# Central_Board.net
KiCad netlist of a schematic drawn in EAGLE
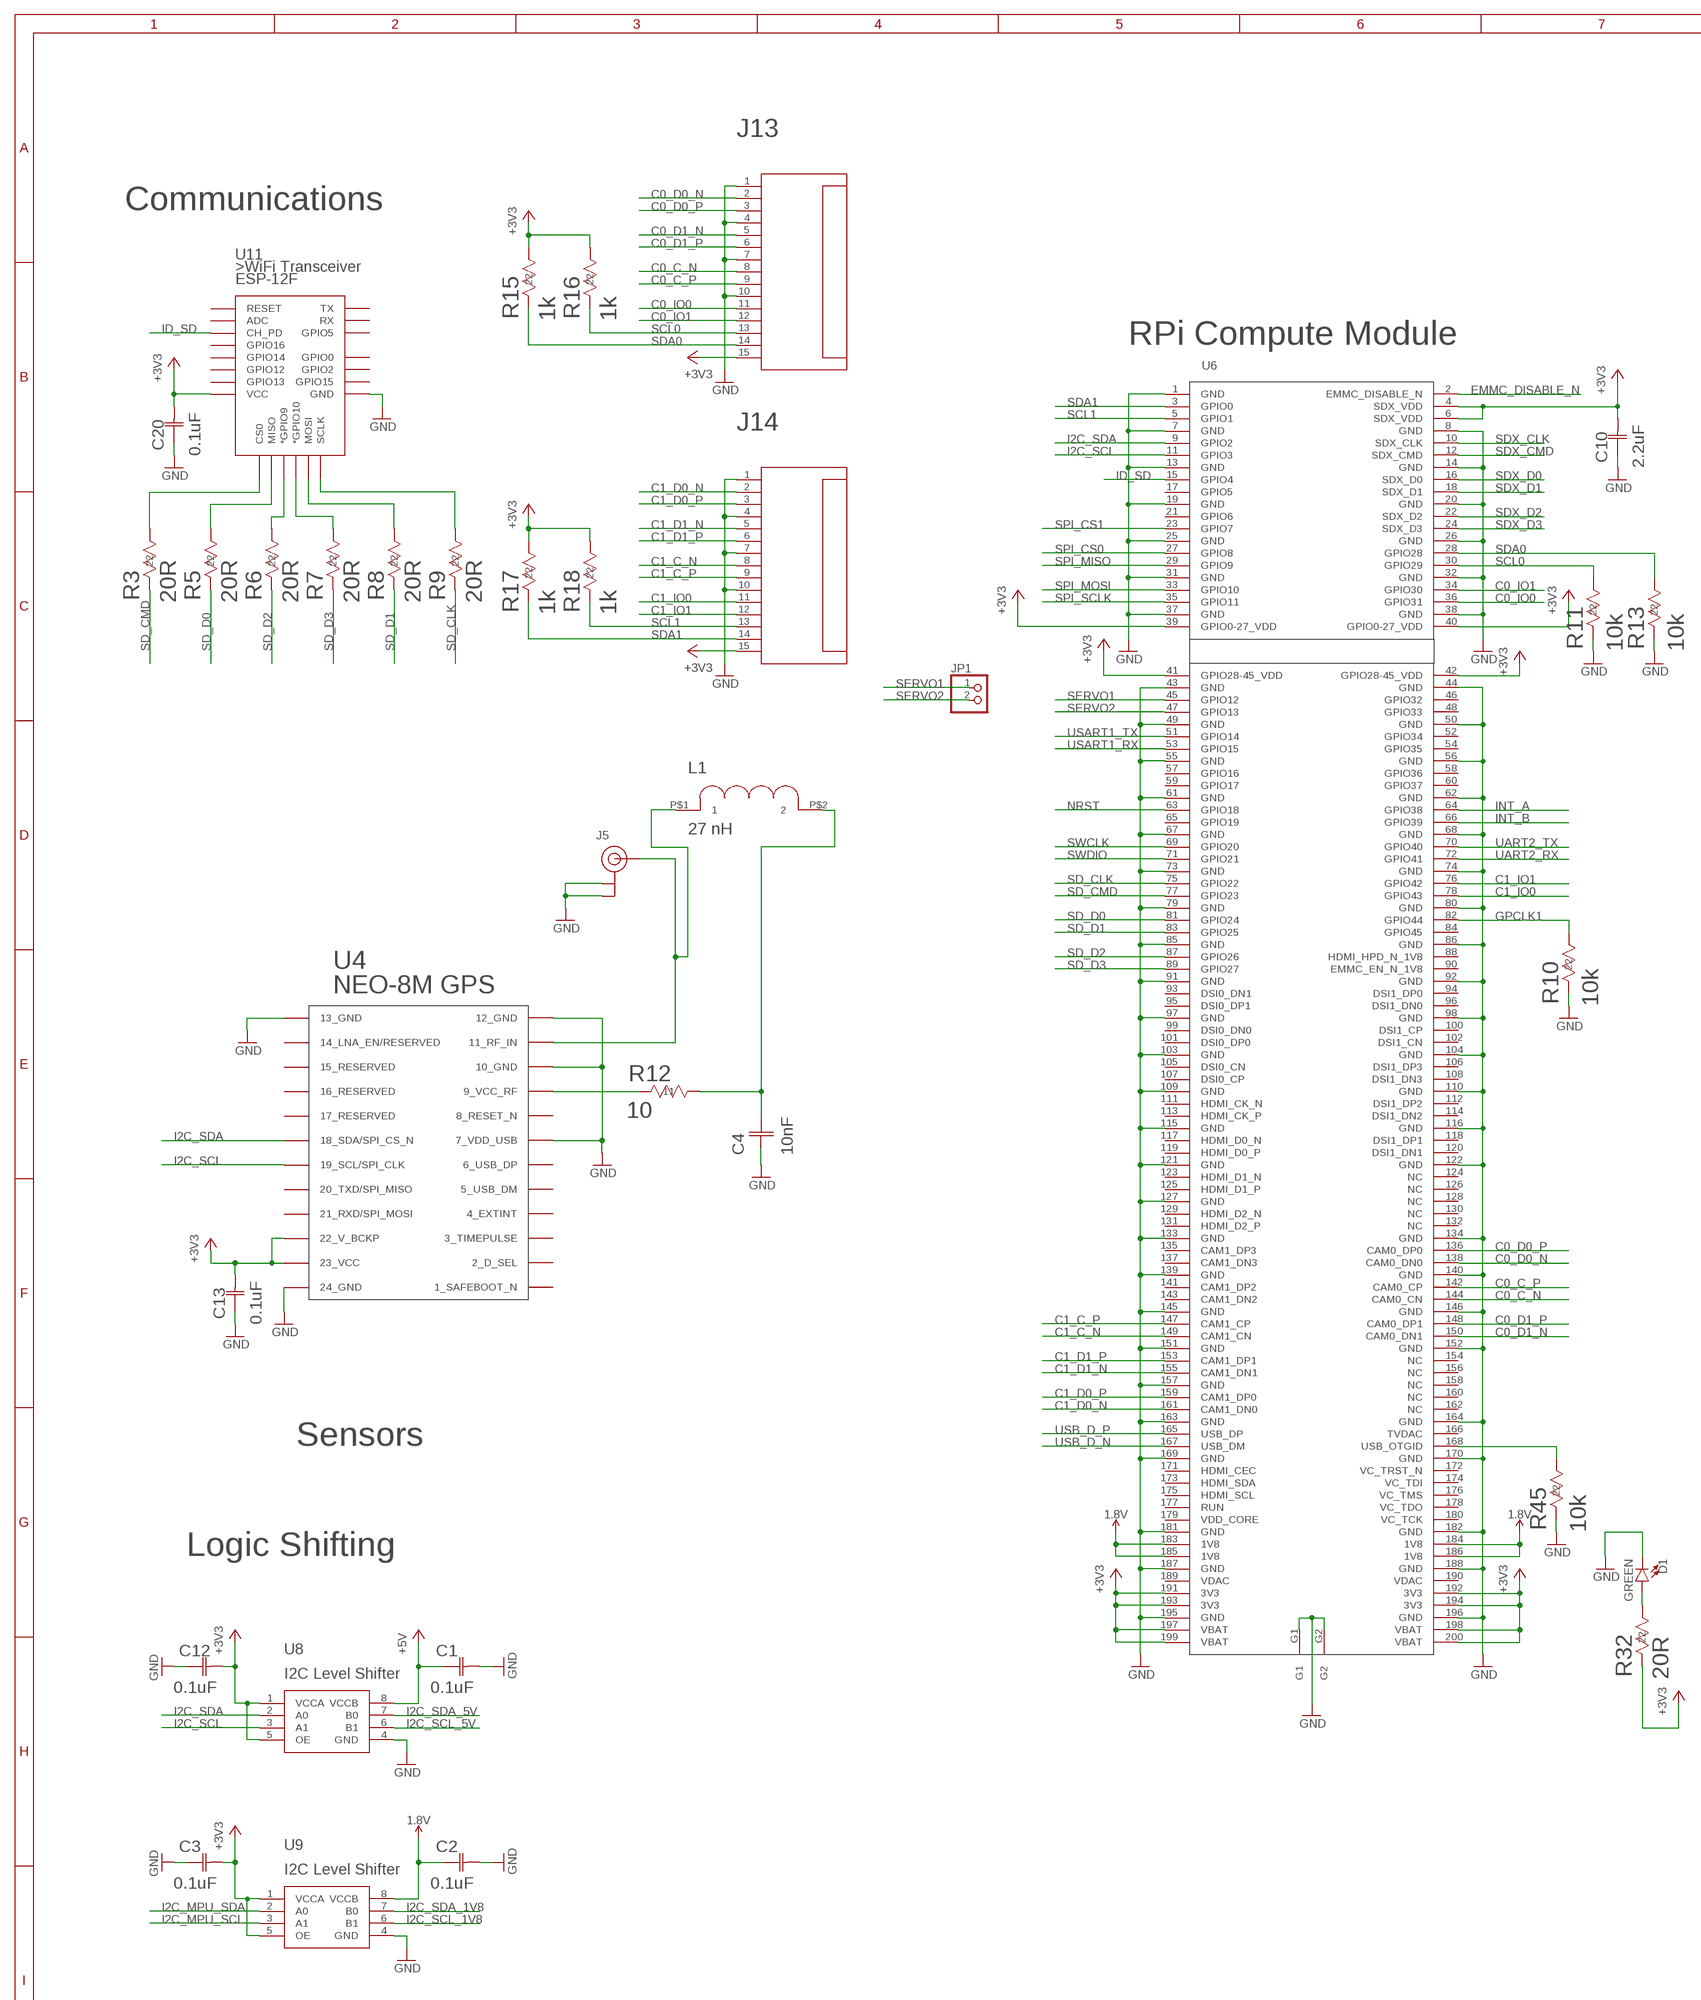
[diagram p0: schematic, sheet 1, part 1 of 2]
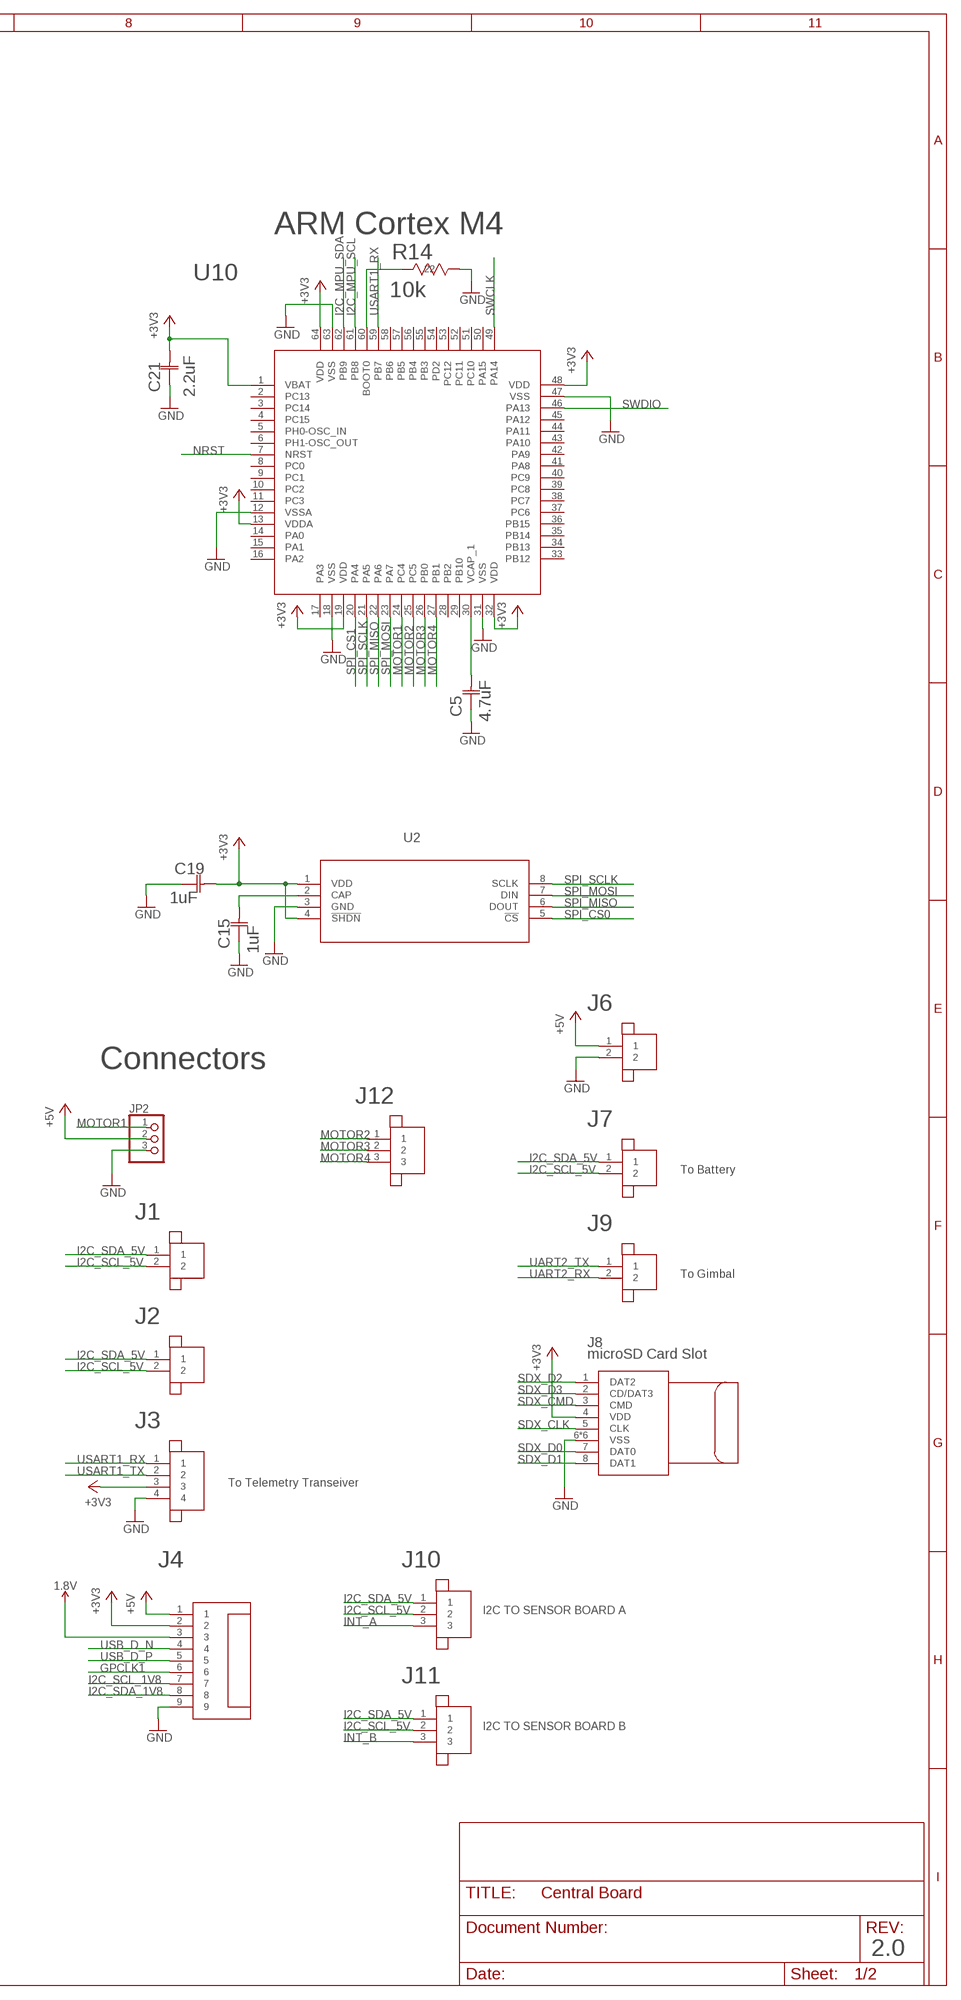
[diagram p1: schematic, sheet 1, part 2 of 2]
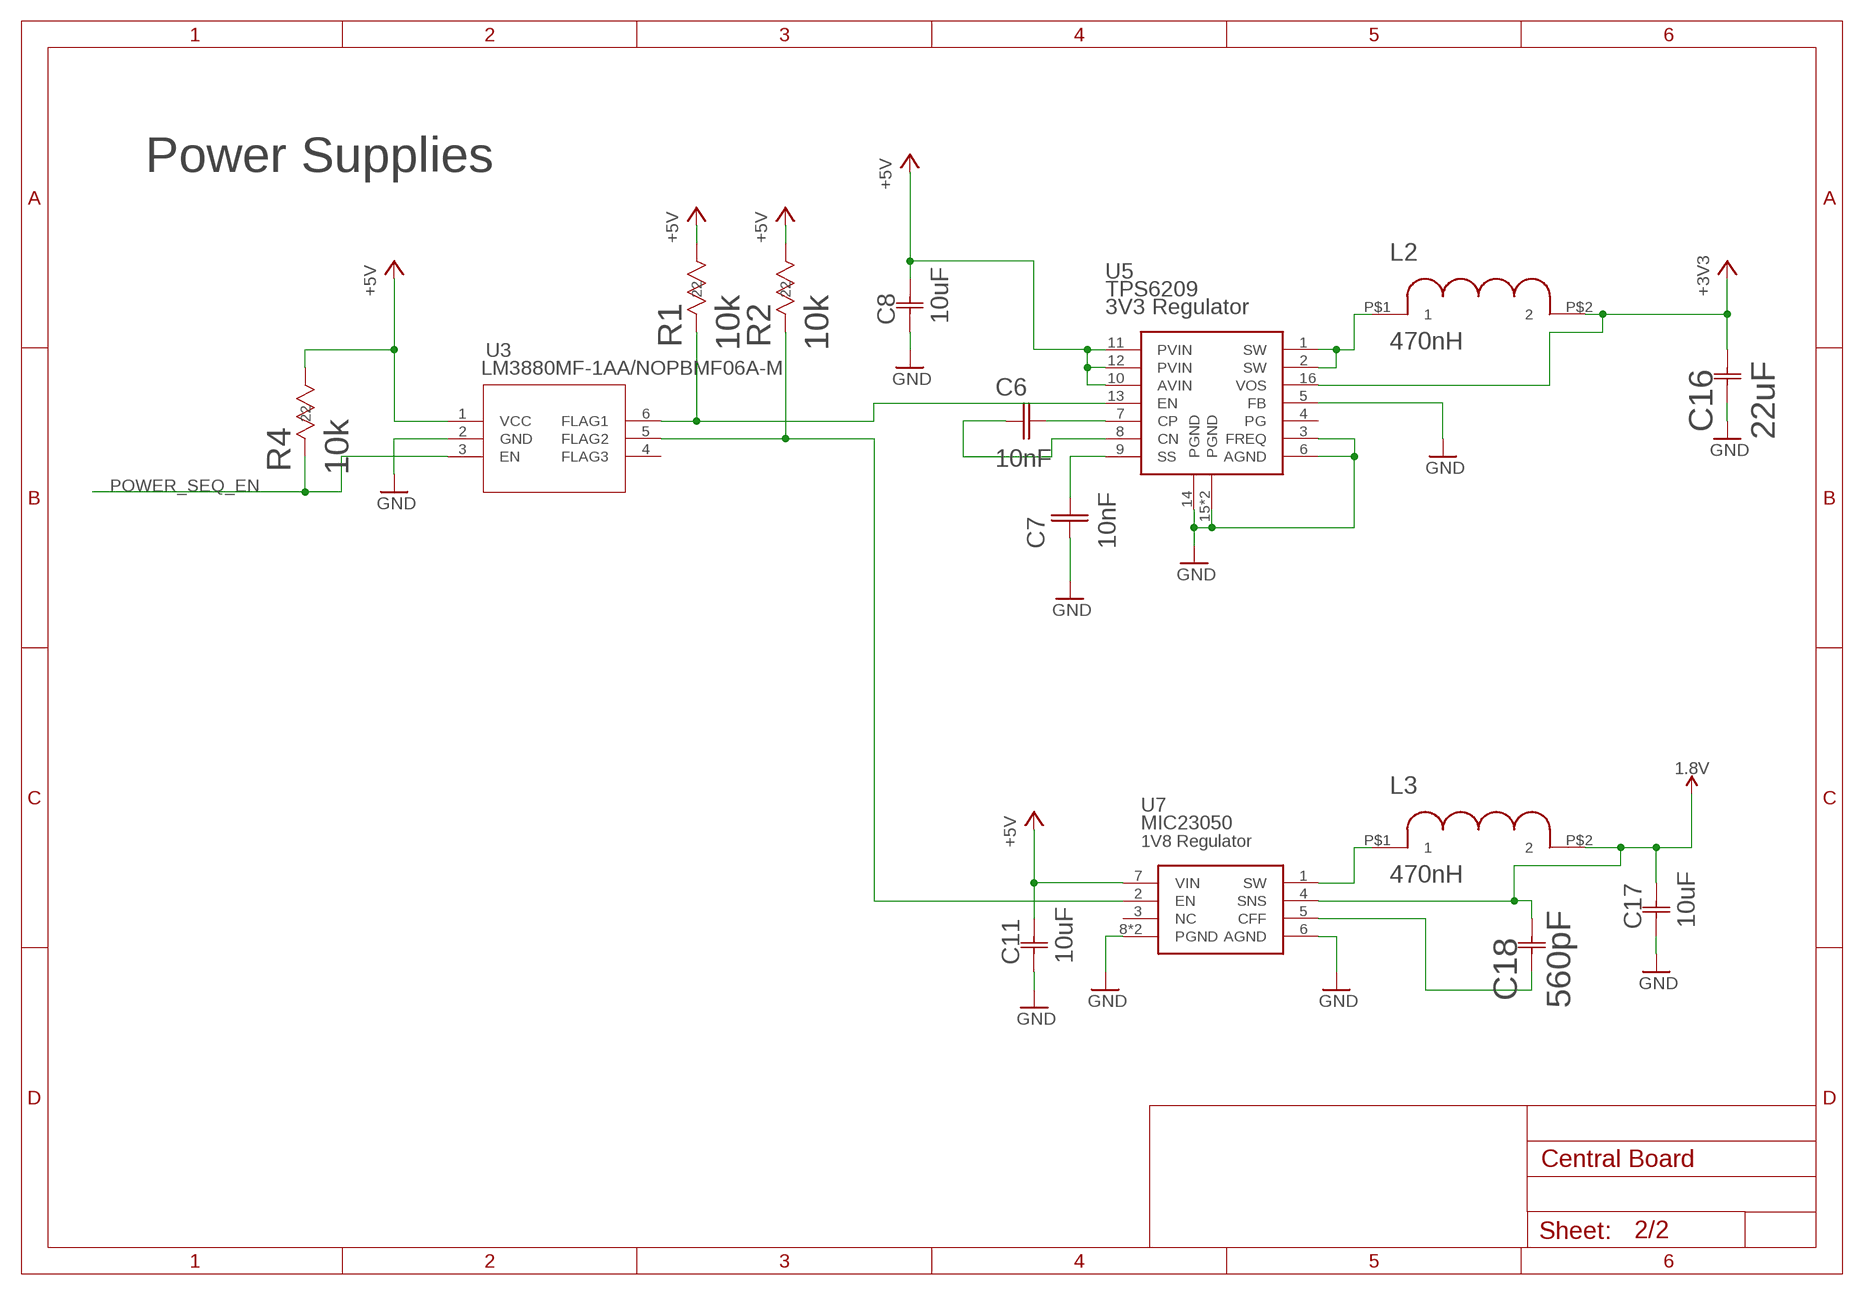
[diagram p2: schematic, sheet 2]

(export (version "E")
  (design (tool "Eeschema 10.0.6"))
  (components
    (comp (ref "C6")
      (value "10nF")
      (footprint "eagle-import:0603_CAPACITOR")
      (libsource (lib "eagle-import") (part "10NF_CAPACITOR"))
    )
    (comp (ref "C7")
      (value "10nF")
      (footprint "eagle-import:0603_CAPACITOR")
      (libsource (lib "eagle-import") (part "10NF_CAPACITOR"))
    )
    (comp (ref "C8")
      (value "10uF")
      (footprint "eagle-import:G-21")
      (fields
        (field (name "MANUFACTURER_PART_NUMBER") "GRM21BR60J106ME19L")
        (field (name "COPYRIGHT") "Copyright C 2015 Accelerated Designs. All rights reserved")
      )
      (libsource (lib "eagle-import") (part "GRM21BR60J106ME19L"))
    )
    (comp (ref "C11")
      (value "10uF")
      (footprint "eagle-import:G-21")
      (fields
        (field (name "MANUFACTURER_PART_NUMBER") "GRM21BR60J106ME19L")
        (field (name "COPYRIGHT") "Copyright C 2015 Accelerated Designs. All rights reserved")
      )
      (libsource (lib "eagle-import") (part "GRM21BR60J106ME19L"))
    )
    (comp (ref "C16")
      (value "22uF")
      (footprint "eagle-import:G-21")
      (fields
        (field (name "MANUFACTURER_PART_NUMBER") "GRM21BR60J226ME39L")
        (field (name "COPYRIGHT") "Copyright C 2015 Accelerated Designs. All rights reserved")
      )
      (libsource (lib "eagle-import") (part "GRM21BR60J226ME39L"))
    )
    (comp (ref "C17")
      (value "10uF")
      (footprint "eagle-import:G-21")
      (fields
        (field (name "MANUFACTURER_PART_NUMBER") "GRM21BR60J106ME19L")
        (field (name "COPYRIGHT") "Copyright C 2015 Accelerated Designs. All rights reserved")
      )
      (libsource (lib "eagle-import") (part "GRM21BR60J106ME19L"))
    )
    (comp (ref "C18")
      (value "560pF")
      (footprint "eagle-import:CC0402N-M")
      (fields (field (name "MANUFACTURER_PART_NUMBER") "CC0402KRX7R9BB561"))
      (libsource (lib "eagle-import") (part "CC0402KRX7R9BB561CC0402N-M"))
    )
    (comp (ref "L2")
      (value "470nH")
      (footprint "eagle-import:1008_INDUCTOR")
      (libsource (lib "eagle-import") (part "470NH_INDUCTOR"))
    )
    (comp (ref "L3")
      (value "470nH")
      (footprint "eagle-import:1008_INDUCTOR")
      (libsource (lib "eagle-import") (part "470NH_INDUCTOR"))
    )
    (comp (ref "R1")
      (value "10k")
      (footprint "eagle-import:RC0805N")
      (fields
        (field (name "DIGIKEYPARTNUMBER") "P10KDATRND")
        (field (name "MANUFACTURER_PART_NUMBER") "ERA6AEB103V")
        (field (name "TOLERANCE") "0.1%")
        (field (name "COPYRIGHT") "Copyright C 2015 Accelerated Designs. All rights reserved")
      )
      (libsource (lib "eagle-import") (part "ERA-6AEB103V"))
    )
    (comp (ref "R2")
      (value "10k")
      (footprint "eagle-import:RC0805N")
      (fields
        (field (name "DIGIKEYPARTNUMBER") "P10KDATRND")
        (field (name "MANUFACTURER_PART_NUMBER") "ERA6AEB103V")
        (field (name "TOLERANCE") "0.1%")
        (field (name "COPYRIGHT") "Copyright C 2015 Accelerated Designs. All rights reserved")
      )
      (libsource (lib "eagle-import") (part "ERA-6AEB103V"))
    )
    (comp (ref "R4")
      (value "10k")
      (footprint "eagle-import:RC0805N")
      (fields
        (field (name "DIGIKEYPARTNUMBER") "P10KDATRND")
        (field (name "MANUFACTURER_PART_NUMBER") "ERA6AEB103V")
        (field (name "TOLERANCE") "0.1%")
        (field (name "COPYRIGHT") "Copyright C 2015 Accelerated Designs. All rights reserved")
      )
      (libsource (lib "eagle-import") (part "ERA-6AEB103V"))
    )
    (comp (ref "U3")
      (value "LM3880MF-1AA/NOPBMF06A-M")
      (footprint "eagle-import:MF06A-M")
      (fields (field (name "MANUFACTURER_PART_NUMBER") "lm3880mf1aaNOPB"))
      (libsource (lib "eagle-import") (part "LM3880MF-1AA/NOPBMF06A-M"))
    )
    (comp (ref "U5")
      (value "TPS6209")
      (footprint "eagle-import:VQFN16")
      (libsource (lib "eagle-import") (part "TPS6209"))
    )
    (comp (ref "U7")
      (value "MIC23050")
      (footprint "eagle-import:MLF(ML)_8PIN")
      (libsource (lib "eagle-import") (part "MIC23050"))
    )
    (comp (ref "C1")
      (value "0.1uF")
      (footprint "eagle-import:0805")
      (fields
        (field (name "MANUFACTURER_PART_NUMBER") "08055C104KAT2A")
        (field (name "COPYRIGHT") "Copyright C 2015 Accelerated Designs. All rights reserved")
      )
      (libsource (lib "eagle-import") (part "08055C104KAT2A"))
    )
    (comp (ref "C2")
      (value "0.1uF")
      (footprint "eagle-import:0805")
      (fields
        (field (name "MANUFACTURER_PART_NUMBER") "08055C104KAT2A")
        (field (name "COPYRIGHT") "Copyright C 2015 Accelerated Designs. All rights reserved")
      )
      (libsource (lib "eagle-import") (part "08055C104KAT2A"))
    )
    (comp (ref "C3")
      (value "0.1uF")
      (footprint "eagle-import:0805")
      (fields
        (field (name "MANUFACTURER_PART_NUMBER") "08055C104KAT2A")
        (field (name "COPYRIGHT") "Copyright C 2015 Accelerated Designs. All rights reserved")
      )
      (libsource (lib "eagle-import") (part "08055C104KAT2A"))
    )
    (comp (ref "C4")
      (value "10nF")
      (footprint "eagle-import:0603_CAPACITOR")
      (libsource (lib "eagle-import") (part "10NF_CAPACITOR"))
    )
    (comp (ref "C5")
      (value "4.7uF")
      (footprint "eagle-import:0603-M")
      (fields (field (name "MANUFACTURER_PART_NUMBER") "06036D475KAT2A"))
      (libsource (lib "eagle-import") (part "06036D475KAT2A0603-M"))
    )
    (comp (ref "C10")
      (value "2.2uF")
      (footprint "eagle-import:G-188-M")
      (fields
        (field (name "MANUFACTURER_PART_NUMBER") "GRM188R61C225KE15J")
        (field (name "COPYRIGHT") "Copyright C 2015 Accelerated Designs. All rights reserved")
      )
      (libsource (lib "eagle-import") (part "GRM188R61C225KE15JG-188-M"))
    )
    (comp (ref "C12")
      (value "0.1uF")
      (footprint "eagle-import:0805")
      (fields
        (field (name "MANUFACTURER_PART_NUMBER") "08055C104KAT2A")
        (field (name "COPYRIGHT") "Copyright C 2015 Accelerated Designs. All rights reserved")
      )
      (libsource (lib "eagle-import") (part "08055C104KAT2A"))
    )
    (comp (ref "C13")
      (value "0.1uF")
      (footprint "eagle-import:0805")
      (fields
        (field (name "MANUFACTURER_PART_NUMBER") "08055C104KAT2A")
        (field (name "COPYRIGHT") "Copyright C 2015 Accelerated Designs. All rights reserved")
      )
      (libsource (lib "eagle-import") (part "08055C104KAT2A"))
    )
    (comp (ref "C15")
      (value "1uF")
      (footprint "eagle-import:YAG_CC0805")
      (fields
        (field (name "MANUFACTURER_PART_NUMBER") "CC0805KKX7R7BB105")
        (field (name "COPYRIGHT") "Copyright C 2015 Accelerated Designs. All rights reserved")
      )
      (libsource (lib "eagle-import") (part "CC0805KKX7R7BB105"))
    )
    (comp (ref "C19")
      (value "1uF")
      (footprint "eagle-import:YAG_CC0805")
      (fields
        (field (name "MANUFACTURER_PART_NUMBER") "CC0805KKX7R7BB105")
        (field (name "COPYRIGHT") "Copyright C 2015 Accelerated Designs. All rights reserved")
      )
      (libsource (lib "eagle-import") (part "CC0805KKX7R7BB105"))
    )
    (comp (ref "C20")
      (value "0.1uF")
      (footprint "eagle-import:0805")
      (fields
        (field (name "MANUFACTURER_PART_NUMBER") "08055C104KAT2A")
        (field (name "COPYRIGHT") "Copyright C 2015 Accelerated Designs. All rights reserved")
      )
      (libsource (lib "eagle-import") (part "08055C104KAT2A"))
    )
    (comp (ref "C21")
      (value "2.2uF")
      (footprint "eagle-import:G-188-M")
      (fields
        (field (name "MANUFACTURER_PART_NUMBER") "GRM188R61C225KE15J")
        (field (name "COPYRIGHT") "Copyright C 2015 Accelerated Designs. All rights reserved")
      )
      (libsource (lib "eagle-import") (part "GRM188R61C225KE15JG-188-M"))
    )
    (comp (ref "D1")
      (value "GREEN")
      (footprint "eagle-import:LED-0603")
      (libsource (lib "eagle-import") (part "LED-GREEN0603"))
    )
    (comp (ref "J1")
      (value "JST_SH_2POS")
      (footprint "eagle-import:JST_SH_2POS")
      (libsource (lib "eagle-import") (part "JST_SH_2POS"))
    )
    (comp (ref "J2")
      (value "JST_SH_2POS")
      (footprint "eagle-import:JST_SH_2POS")
      (libsource (lib "eagle-import") (part "JST_SH_2POS"))
    )
    (comp (ref "J3")
      (value "JST_SH_4POS")
      (footprint "eagle-import:JST_SH_4POS")
      (libsource (lib "eagle-import") (part "JST_SH_4POS"))
    )
    (comp (ref "J4")
      (value "9POS_FFC_CONNECTOR")
      (footprint "eagle-import:9POS_FFC_CONNECTOR")
      (libsource (lib "eagle-import") (part "9POS_FFC_CONNECTOR"))
    )
    (comp (ref "J5")
      (value "U.FL")
      (footprint "eagle-import:U.FL")
      (libsource (lib "eagle-import") (part "U.FL"))
    )
    (comp (ref "J6")
      (value "JST_SH_2POS")
      (footprint "eagle-import:JST_SH_2POS")
      (libsource (lib "eagle-import") (part "JST_SH_2POS"))
    )
    (comp (ref "J7")
      (value "JST_SH_2POS")
      (footprint "eagle-import:JST_SH_2POS")
      (libsource (lib "eagle-import") (part "JST_SH_2POS"))
    )
    (comp (ref "J8")
      (value "MICROSD")
      (footprint "eagle-import:MICROSD")
      (libsource (lib "eagle-import") (part "MICROSD"))
    )
    (comp (ref "J9")
      (value "JST_SH_2POS")
      (footprint "eagle-import:JST_SH_2POS")
      (libsource (lib "eagle-import") (part "JST_SH_2POS"))
    )
    (comp (ref "J10")
      (value "JST_SH_3POS")
      (footprint "eagle-import:JST_SH_3POS")
      (libsource (lib "eagle-import") (part "JST_SH_3POS"))
    )
    (comp (ref "J11")
      (value "JST_SH_3POS")
      (footprint "eagle-import:JST_SH_3POS")
      (libsource (lib "eagle-import") (part "JST_SH_3POS"))
    )
    (comp (ref "J12")
      (value "JST_SH_3POS")
      (footprint "eagle-import:JST_SH_3POS")
      (libsource (lib "eagle-import") (part "JST_SH_3POS"))
    )
    (comp (ref "J13")
      (value "0526101572_15ZIF_CONNECTOR")
      (footprint "eagle-import:15POS_FFC_CONNECTOR")
      (libsource (lib "eagle-import") (part "0526101572_15ZIF_CONNECTOR"))
    )
    (comp (ref "J14")
      (value "0526101572_15ZIF_CONNECTOR")
      (footprint "eagle-import:15POS_FFC_CONNECTOR")
      (libsource (lib "eagle-import") (part "0526101572_15ZIF_CONNECTOR"))
    )
    (comp (ref "JP1")
      (value "PINHD-1X2")
      (footprint "eagle-import:1X02")
      (libsource (lib "eagle-import") (part "PINHD-1X2"))
    )
    (comp (ref "JP2")
      (value "PINHD-1X3")
      (footprint "eagle-import:1X03")
      (libsource (lib "eagle-import") (part "PINHD-1X3"))
    )
    (comp (ref "L1")
      (value "27 nH")
      (footprint "eagle-import:0402_INDUCTOR")
      (libsource (lib "eagle-import") (part "27NH_INDUCTOR"))
    )
    (comp (ref "R3")
      (value "20R")
      (footprint "eagle-import:RC0603N-M")
      (fields (field (name "MANUFACTURER_PART_NUMBER") "RC0603JR0720RL"))
      (libsource (lib "eagle-import") (part "RC0603JR-0720RLRC0603N-M"))
    )
    (comp (ref "R5")
      (value "20R")
      (footprint "eagle-import:RC0603N-M")
      (fields (field (name "MANUFACTURER_PART_NUMBER") "RC0603JR0720RL"))
      (libsource (lib "eagle-import") (part "RC0603JR-0720RLRC0603N-M"))
    )
    (comp (ref "R6")
      (value "20R")
      (footprint "eagle-import:RC0603N-M")
      (fields (field (name "MANUFACTURER_PART_NUMBER") "RC0603JR0720RL"))
      (libsource (lib "eagle-import") (part "RC0603JR-0720RLRC0603N-M"))
    )
    (comp (ref "R7")
      (value "20R")
      (footprint "eagle-import:RC0603N-M")
      (fields (field (name "MANUFACTURER_PART_NUMBER") "RC0603JR0720RL"))
      (libsource (lib "eagle-import") (part "RC0603JR-0720RLRC0603N-M"))
    )
    (comp (ref "R8")
      (value "20R")
      (footprint "eagle-import:RC0603N-M")
      (fields (field (name "MANUFACTURER_PART_NUMBER") "RC0603JR0720RL"))
      (libsource (lib "eagle-import") (part "RC0603JR-0720RLRC0603N-M"))
    )
    (comp (ref "R9")
      (value "20R")
      (footprint "eagle-import:RC0603N-M")
      (fields (field (name "MANUFACTURER_PART_NUMBER") "RC0603JR0720RL"))
      (libsource (lib "eagle-import") (part "RC0603JR-0720RLRC0603N-M"))
    )
    (comp (ref "R10")
      (value "10k")
      (footprint "eagle-import:RC0805N")
      (fields
        (field (name "DIGIKEYPARTNUMBER") "P10KDATRND")
        (field (name "MANUFACTURER_PART_NUMBER") "ERA6AEB103V")
        (field (name "TOLERANCE") "0.1%")
        (field (name "COPYRIGHT") "Copyright C 2015 Accelerated Designs. All rights reserved")
      )
      (libsource (lib "eagle-import") (part "ERA-6AEB103V"))
    )
    (comp (ref "R11")
      (value "10k")
      (footprint "eagle-import:RC0805N")
      (fields
        (field (name "DIGIKEYPARTNUMBER") "P10KDATRND")
        (field (name "MANUFACTURER_PART_NUMBER") "ERA6AEB103V")
        (field (name "TOLERANCE") "0.1%")
        (field (name "COPYRIGHT") "Copyright C 2015 Accelerated Designs. All rights reserved")
      )
      (libsource (lib "eagle-import") (part "ERA-6AEB103V"))
    )
    (comp (ref "R12")
      (value "10")
      (footprint "eagle-import:STA_RNCP0805-M")
      (fields
        (field (name "MANUFACTURER_PART_NUMBER") "RNCP0805FTD10R0")
        (field (name "COPYRIGHT") "Copyright C 2015 Accelerated Designs. All rights reserved")
      )
      (libsource (lib "eagle-import") (part "RNCP0805FTD10R0STA_RNCP0805-M"))
    )
    (comp (ref "R13")
      (value "10k")
      (footprint "eagle-import:RC0805N")
      (fields
        (field (name "DIGIKEYPARTNUMBER") "P10KDATRND")
        (field (name "MANUFACTURER_PART_NUMBER") "ERA6AEB103V")
        (field (name "TOLERANCE") "0.1%")
        (field (name "COPYRIGHT") "Copyright C 2015 Accelerated Designs. All rights reserved")
      )
      (libsource (lib "eagle-import") (part "ERA-6AEB103V"))
    )
    (comp (ref "R14")
      (value "10k")
      (footprint "eagle-import:RC0805N")
      (fields
        (field (name "DIGIKEYPARTNUMBER") "P10KDATRND")
        (field (name "MANUFACTURER_PART_NUMBER") "ERA6AEB103V")
        (field (name "TOLERANCE") "0.1%")
        (field (name "COPYRIGHT") "Copyright C 2015 Accelerated Designs. All rights reserved")
      )
      (libsource (lib "eagle-import") (part "ERA-6AEB103V"))
    )
    (comp (ref "R15")
      (value "1k")
      (footprint "eagle-import:RC0603N-M")
      (fields
        (field (name "DIGIKEYPARTNUMBER") "3111.0KGRTRND")
        (field (name "MANUFACTURER_PART_NUMBER") "RC0603JR071KL")
        (field (name "NEWARKPARTNUMBER") "14M7231")
        (field (name "COPYRIGHT") "Copyright C 2015 Accelerated Designs. All rights reserved")
      )
      (libsource (lib "eagle-import") (part "RC0603JR-071KLRC0603N-M"))
    )
    (comp (ref "R16")
      (value "1k")
      (footprint "eagle-import:RC0603N-M")
      (fields
        (field (name "DIGIKEYPARTNUMBER") "3111.0KGRTRND")
        (field (name "MANUFACTURER_PART_NUMBER") "RC0603JR071KL")
        (field (name "NEWARKPARTNUMBER") "14M7231")
        (field (name "COPYRIGHT") "Copyright C 2015 Accelerated Designs. All rights reserved")
      )
      (libsource (lib "eagle-import") (part "RC0603JR-071KLRC0603N-M"))
    )
    (comp (ref "R17")
      (value "1k")
      (footprint "eagle-import:RC0603N-M")
      (fields
        (field (name "DIGIKEYPARTNUMBER") "3111.0KGRTRND")
        (field (name "MANUFACTURER_PART_NUMBER") "RC0603JR071KL")
        (field (name "NEWARKPARTNUMBER") "14M7231")
        (field (name "COPYRIGHT") "Copyright C 2015 Accelerated Designs. All rights reserved")
      )
      (libsource (lib "eagle-import") (part "RC0603JR-071KLRC0603N-M"))
    )
    (comp (ref "R18")
      (value "1k")
      (footprint "eagle-import:RC0603N-M")
      (fields
        (field (name "DIGIKEYPARTNUMBER") "3111.0KGRTRND")
        (field (name "MANUFACTURER_PART_NUMBER") "RC0603JR071KL")
        (field (name "NEWARKPARTNUMBER") "14M7231")
        (field (name "COPYRIGHT") "Copyright C 2015 Accelerated Designs. All rights reserved")
      )
      (libsource (lib "eagle-import") (part "RC0603JR-071KLRC0603N-M"))
    )
    (comp (ref "R32")
      (value "20R")
      (footprint "eagle-import:RC0603N-M")
      (fields (field (name "MANUFACTURER_PART_NUMBER") "RC0603JR0720RL"))
      (libsource (lib "eagle-import") (part "RC0603JR-0720RLRC0603N-M"))
    )
    (comp (ref "R45")
      (value "10k")
      (footprint "eagle-import:RC0805N")
      (fields
        (field (name "DIGIKEYPARTNUMBER") "P10KDATRND")
        (field (name "MANUFACTURER_PART_NUMBER") "ERA6AEB103V")
        (field (name "TOLERANCE") "0.1%")
        (field (name "COPYRIGHT") "Copyright C 2015 Accelerated Designs. All rights reserved")
      )
      (libsource (lib "eagle-import") (part "ERA-6AEB103V"))
    )
    (comp (ref "U2")
      (value "MPL115A1LGA8-M")
      (footprint "eagle-import:LGA8-M")
      (fields (field (name "MANUFACTURER_PART_NUMBER") "mpl115a1"))
      (libsource (lib "eagle-import") (part "MPL115A1LGA8-M"))
    )
    (comp (ref "U4")
      (value "NEO-M8")
      (footprint "eagle-import:NEO-M8")
      (libsource (lib "eagle-import") (part "NEO-M8"))
    )
    (comp (ref "U6")
      (value "COMPUTE_MODULE")
      (footprint "eagle-import:SO-DIMM")
      (libsource (lib "eagle-import") (part "COMPUTE_MODULE"))
    )
    (comp (ref "U8")
      (value "FXMAR2102")
      (footprint "eagle-import:8-UMLP")
      (libsource (lib "eagle-import") (part "FXMAR2102"))
    )
    (comp (ref "U9")
      (value "FXMAR2102")
      (footprint "eagle-import:8-UMLP")
      (libsource (lib "eagle-import") (part "FXMAR2102"))
    )
    (comp (ref "U10")
      (value "STM32F446")
      (footprint "eagle-import:LQFP64")
      (libsource (lib "eagle-import") (part "STM32F446"))
    )
    (comp (ref "U11")
      (value "ESP12ESMD")
      (footprint "eagle-import:ESP12E-SMD")
      (libsource (lib "eagle-import") (part "ESP12ESMD"))
    )
  )
  (nets
    (net (code "1") (name "+3V3") (class "Default")
      (node (ref "C10") (pin "2") (pinfunction "22_2") (pintype "passive"))
      (node (ref "C12") (pin "2") (pinfunction "2_2") (pintype "passive"))
      (node (ref "C13") (pin "2") (pinfunction "2_2") (pintype "passive"))
      (node (ref "C16") (pin "2") (pinfunction "22_2") (pintype "passive"))
      (node (ref "C19") (pin "2") (pinfunction "22_2") (pintype "passive"))
      (node (ref "C20") (pin "2") (pinfunction "2_2") (pintype "passive"))
      (node (ref "C21") (pin "2") (pinfunction "22_2") (pintype "passive"))
      (node (ref "C3") (pin "2") (pinfunction "2_2") (pintype "passive"))
      (node (ref "J13") (pin "15") (pinfunction "15_15") (pintype "bidirectional"))
      (node (ref "J14") (pin "15") (pinfunction "15_15") (pintype "bidirectional"))
      (node (ref "J3") (pin "3") (pinfunction "3_3") (pintype "bidirectional"))
      (node (ref "J4") (pin "2") (pinfunction "2_2") (pintype "bidirectional"))
      (node (ref "J8") (pin "4") (pinfunction "VDD_4") (pintype "bidirectional"))
      (node (ref "L2") (pin "P$2") (pinfunction "2_P$2") (pintype "passive"))
      (node (ref "R15") (pin "1") (pinfunction "11_1") (pintype "passive"))
      (node (ref "R16") (pin "1") (pinfunction "11_1") (pintype "passive"))
      (node (ref "R17") (pin "1") (pinfunction "11_1") (pintype "passive"))
      (node (ref "R18") (pin "1") (pinfunction "11_1") (pintype "passive"))
      (node (ref "R32") (pin "2") (pinfunction "22_2") (pintype "passive"))
      (node (ref "U10") (pin "1") (pinfunction "VBAT_1") (pintype "bidirectional"))
      (node (ref "U10") (pin "13") (pinfunction "VDDA_13") (pintype "bidirectional"))
      (node (ref "U10") (pin "19") (pinfunction "VDD_19") (pintype "bidirectional"))
      (node (ref "U10") (pin "32") (pinfunction "VDD_32") (pintype "bidirectional"))
      (node (ref "U10") (pin "48") (pinfunction "VDD_48") (pintype "bidirectional"))
      (node (ref "U10") (pin "64") (pinfunction "VDD_64") (pintype "bidirectional"))
      (node (ref "U11") (pin "VCC") (pinfunction "VCC_VCC") (pintype "bidirectional"))
      (node (ref "U2") (pin "1") (pinfunction "VDD_1") (pintype "power_in"))
      (node (ref "U2") (pin "4") (pinfunction "~{SHDN}_4") (pintype "passive"))
      (node (ref "U4") (pin "22") (pinfunction "22_V_BCKP_22") (pintype "bidirectional"))
      (node (ref "U4") (pin "23") (pinfunction "23_VCC_23") (pintype "bidirectional"))
      (node (ref "U5") (pin "16") (pinfunction "VOS_16") (pintype "bidirectional"))
      (node (ref "U6") (pin "191") (pinfunction "3V3_191") (pintype "bidirectional"))
      (node (ref "U6") (pin "192") (pinfunction "3V3_192") (pintype "bidirectional"))
      (node (ref "U6") (pin "193") (pinfunction "3V3_193") (pintype "bidirectional"))
      (node (ref "U6") (pin "194") (pinfunction "3V3_194") (pintype "bidirectional"))
      (node (ref "U6") (pin "197") (pinfunction "VBAT_197") (pintype "bidirectional"))
      (node (ref "U6") (pin "198") (pinfunction "VBAT_198") (pintype "bidirectional"))
      (node (ref "U6") (pin "199") (pinfunction "VBAT_199") (pintype "bidirectional"))
      (node (ref "U6") (pin "200") (pinfunction "VBAT_200") (pintype "bidirectional"))
      (node (ref "U6") (pin "39") (pinfunction "GPIO0-27_VDD_39") (pintype "bidirectional"))
      (node (ref "U6") (pin "4") (pinfunction "SDX_VDD_4") (pintype "bidirectional"))
      (node (ref "U6") (pin "40") (pinfunction "GPIO0-27_VDD_40") (pintype "bidirectional"))
      (node (ref "U6") (pin "41") (pinfunction "GPIO28-45_VDD_41") (pintype "bidirectional"))
      (node (ref "U6") (pin "42") (pinfunction "GPIO28-45_VDD_42") (pintype "bidirectional"))
      (node (ref "U6") (pin "6") (pinfunction "SDX_VDD_6") (pintype "bidirectional"))
      (node (ref "U8") (pin "1") (pinfunction "VCCA_1") (pintype "bidirectional"))
      (node (ref "U8") (pin "5") (pinfunction "OE_5") (pintype "bidirectional"))
      (node (ref "U9") (pin "1") (pinfunction "VCCA_1") (pintype "bidirectional"))
      (node (ref "U9") (pin "5") (pinfunction "OE_5") (pintype "bidirectional"))
    )
    (net (code "2") (name "+5V") (class "Default")
      (node (ref "C1") (pin "1") (pinfunction "1_1") (pintype "passive"))
      (node (ref "C11") (pin "2") (pinfunction "22_2") (pintype "passive"))
      (node (ref "C8") (pin "2") (pinfunction "22_2") (pintype "passive"))
      (node (ref "J4") (pin "1") (pinfunction "1_1") (pintype "bidirectional"))
      (node (ref "J6") (pin "1") (pinfunction "1_1") (pintype "bidirectional"))
      (node (ref "JP2") (pin "2") (pinfunction "2_2") (pintype "passive"))
      (node (ref "R1") (pin "1") (pinfunction "11_1") (pintype "passive"))
      (node (ref "R2") (pin "1") (pinfunction "11_1") (pintype "passive"))
      (node (ref "R4") (pin "1") (pinfunction "11_1") (pintype "passive"))
      (node (ref "U3") (pin "1") (pinfunction "VCC_1") (pintype "power_in"))
      (node (ref "U5") (pin "10") (pinfunction "AVIN_10") (pintype "bidirectional"))
      (node (ref "U5") (pin "11") (pinfunction "PVIN_11") (pintype "bidirectional"))
      (node (ref "U5") (pin "12") (pinfunction "PVIN_12") (pintype "bidirectional"))
      (node (ref "U7") (pin "7") (pinfunction "VIN_7") (pintype "bidirectional"))
      (node (ref "U8") (pin "8") (pinfunction "VCCB_8") (pintype "bidirectional"))
    )
    (net (code "3") (name "1.8V") (class "Default")
      (node (ref "C17") (pin "2") (pinfunction "22_2") (pintype "passive"))
      (node (ref "C18") (pin "2") (pinfunction "22_2") (pintype "passive"))
      (node (ref "C2") (pin "1") (pinfunction "1_1") (pintype "passive"))
      (node (ref "J4") (pin "3") (pinfunction "3_3") (pintype "bidirectional"))
      (node (ref "L3") (pin "P$2") (pinfunction "2_P$2") (pintype "passive"))
      (node (ref "U6") (pin "183") (pinfunction "1V8_183") (pintype "bidirectional"))
      (node (ref "U6") (pin "184") (pinfunction "1V8_184") (pintype "bidirectional"))
      (node (ref "U6") (pin "185") (pinfunction "1V8_185") (pintype "bidirectional"))
      (node (ref "U6") (pin "186") (pinfunction "1V8_186") (pintype "bidirectional"))
      (node (ref "U7") (pin "4") (pinfunction "SNS_4") (pintype "bidirectional"))
      (node (ref "U9") (pin "8") (pinfunction "VCCB_8") (pintype "bidirectional"))
    )
    (net (code "4") (name "C0_C_N") (class "Default")
      (node (ref "J13") (pin "8") (pinfunction "8_8") (pintype "bidirectional"))
      (node (ref "U6") (pin "144") (pinfunction "CAM0_CN_144") (pintype "bidirectional"))
    )
    (net (code "5") (name "C0_C_P") (class "Default")
      (node (ref "J13") (pin "9") (pinfunction "9_9") (pintype "bidirectional"))
      (node (ref "U6") (pin "142") (pinfunction "CAM0_CP_142") (pintype "bidirectional"))
    )
    (net (code "6") (name "C0_D0_N") (class "Default")
      (node (ref "J13") (pin "2") (pinfunction "2_2") (pintype "bidirectional"))
      (node (ref "U6") (pin "138") (pinfunction "CAM0_DN0_138") (pintype "bidirectional"))
    )
    (net (code "7") (name "C0_D0_P") (class "Default")
      (node (ref "J13") (pin "3") (pinfunction "3_3") (pintype "bidirectional"))
      (node (ref "U6") (pin "136") (pinfunction "CAM0_DP0_136") (pintype "bidirectional"))
    )
    (net (code "8") (name "C0_D1_N") (class "Default")
      (node (ref "J13") (pin "5") (pinfunction "5_5") (pintype "bidirectional"))
      (node (ref "U6") (pin "150") (pinfunction "CAM0_DN1_150") (pintype "bidirectional"))
    )
    (net (code "9") (name "C0_D1_P") (class "Default")
      (node (ref "J13") (pin "6") (pinfunction "6_6") (pintype "bidirectional"))
      (node (ref "U6") (pin "148") (pinfunction "CAM0_DP1_148") (pintype "bidirectional"))
    )
    (net (code "10") (name "C0_IO0") (class "Default")
      (node (ref "J13") (pin "11") (pinfunction "11_11") (pintype "bidirectional"))
      (node (ref "U6") (pin "36") (pinfunction "GPIO31_36") (pintype "bidirectional"))
    )
    (net (code "11") (name "C0_IO1") (class "Default")
      (node (ref "J13") (pin "12") (pinfunction "12_12") (pintype "bidirectional"))
      (node (ref "U6") (pin "34") (pinfunction "GPIO30_34") (pintype "bidirectional"))
    )
    (net (code "12") (name "C1_C_N") (class "Default")
      (node (ref "J14") (pin "8") (pinfunction "8_8") (pintype "bidirectional"))
      (node (ref "U6") (pin "149") (pinfunction "CAM1_CN_149") (pintype "bidirectional"))
    )
    (net (code "13") (name "C1_C_P") (class "Default")
      (node (ref "J14") (pin "9") (pinfunction "9_9") (pintype "bidirectional"))
      (node (ref "U6") (pin "147") (pinfunction "CAM1_CP_147") (pintype "bidirectional"))
    )
    (net (code "14") (name "C1_D0_N") (class "Default")
      (node (ref "J14") (pin "2") (pinfunction "2_2") (pintype "bidirectional"))
      (node (ref "U6") (pin "161") (pinfunction "CAM1_DN0_161") (pintype "bidirectional"))
    )
    (net (code "15") (name "C1_D0_P") (class "Default")
      (node (ref "J14") (pin "3") (pinfunction "3_3") (pintype "bidirectional"))
      (node (ref "U6") (pin "159") (pinfunction "CAM1_DP0_159") (pintype "bidirectional"))
    )
    (net (code "16") (name "C1_D1_N") (class "Default")
      (node (ref "J14") (pin "5") (pinfunction "5_5") (pintype "bidirectional"))
      (node (ref "U6") (pin "155") (pinfunction "CAM1_DN1_155") (pintype "bidirectional"))
    )
    (net (code "17") (name "C1_D1_P") (class "Default")
      (node (ref "J14") (pin "6") (pinfunction "6_6") (pintype "bidirectional"))
      (node (ref "U6") (pin "153") (pinfunction "CAM1_DP1_153") (pintype "bidirectional"))
    )
    (net (code "18") (name "C1_IO0") (class "Default")
      (node (ref "J14") (pin "11") (pinfunction "11_11") (pintype "bidirectional"))
      (node (ref "U6") (pin "78") (pinfunction "GPIO43_78") (pintype "bidirectional"))
    )
    (net (code "19") (name "C1_IO1") (class "Default")
      (node (ref "J14") (pin "12") (pinfunction "12_12") (pintype "bidirectional"))
      (node (ref "U6") (pin "76") (pinfunction "GPIO42_76") (pintype "bidirectional"))
    )
    (net (code "20") (name "EMMC_DISABLE_N") (class "Default")
      (node (ref "U6") (pin "2") (pinfunction "EMMC_DISABLE_N_2") (pintype "bidirectional"))
    )
    (net (code "21") (name "GND") (class "Default")
      (node (ref "C1") (pin "2") (pinfunction "2_2") (pintype "passive"))
      (node (ref "C10") (pin "1") (pinfunction "11_1") (pintype "passive"))
      (node (ref "C11") (pin "1") (pinfunction "11_1") (pintype "passive"))
      (node (ref "C12") (pin "1") (pinfunction "1_1") (pintype "passive"))
      (node (ref "C13") (pin "1") (pinfunction "1_1") (pintype "passive"))
      (node (ref "C15") (pin "1") (pinfunction "11_1") (pintype "passive"))
      (node (ref "C16") (pin "1") (pinfunction "11_1") (pintype "passive"))
      (node (ref "C17") (pin "1") (pinfunction "11_1") (pintype "passive"))
      (node (ref "C19") (pin "1") (pinfunction "11_1") (pintype "passive"))
      (node (ref "C2") (pin "2") (pinfunction "2_2") (pintype "passive"))
      (node (ref "C20") (pin "1") (pinfunction "1_1") (pintype "passive"))
      (node (ref "C21") (pin "1") (pinfunction "11_1") (pintype "passive"))
      (node (ref "C3") (pin "1") (pinfunction "1_1") (pintype "passive"))
      (node (ref "C4") (pin "1") (pinfunction "1_1") (pintype "bidirectional"))
      (node (ref "C5") (pin "1") (pinfunction "1_1") (pintype "passive"))
      (node (ref "C7") (pin "1") (pinfunction "1_1") (pintype "bidirectional"))
      (node (ref "C8") (pin "1") (pinfunction "11_1") (pintype "passive"))
      (node (ref "D1") (pin "C") (pinfunction "C_C") (pintype "passive"))
      (node (ref "J13") (pin "1") (pinfunction "1_1") (pintype "bidirectional"))
      (node (ref "J13") (pin "10") (pinfunction "10_10") (pintype "bidirectional"))
      (node (ref "J13") (pin "4") (pinfunction "4_4") (pintype "bidirectional"))
      (node (ref "J13") (pin "7") (pinfunction "7_7") (pintype "bidirectional"))
      (node (ref "J14") (pin "1") (pinfunction "1_1") (pintype "bidirectional"))
      (node (ref "J14") (pin "10") (pinfunction "10_10") (pintype "bidirectional"))
      (node (ref "J14") (pin "4") (pinfunction "4_4") (pintype "bidirectional"))
      (node (ref "J14") (pin "7") (pinfunction "7_7") (pintype "bidirectional"))
      (node (ref "J3") (pin "4") (pinfunction "4_4") (pintype "bidirectional"))
      (node (ref "J4") (pin "9") (pinfunction "9_9") (pintype "bidirectional"))
      (node (ref "J5") (pin "P$1") (pinfunction "GND_P$1") (pintype "bidirectional"))
      (node (ref "J5") (pin "P$2") (pinfunction "GND_P$2") (pintype "bidirectional"))
      (node (ref "J6") (pin "2") (pinfunction "2_2") (pintype "bidirectional"))
      (node (ref "J8") (pin "10") (pinfunction "VSS_10") (pintype "bidirectional"))
      (node (ref "J8") (pin "11") (pinfunction "VSS_11") (pintype "bidirectional"))
      (node (ref "J8") (pin "12") (pinfunction "VSS_12") (pintype "bidirectional"))
      (node (ref "J8") (pin "13") (pinfunction "VSS_13") (pintype "bidirectional"))
      (node (ref "J8") (pin "6") (pinfunction "VSS_6") (pintype "bidirectional"))
      (node (ref "J8") (pin "9") (pinfunction "VSS_9") (pintype "bidirectional"))
      (node (ref "JP2") (pin "3") (pinfunction "3_3") (pintype "passive"))
      (node (ref "R10") (pin "2") (pinfunction "22_2") (pintype "passive"))
      (node (ref "R11") (pin "2") (pinfunction "22_2") (pintype "passive"))
      (node (ref "R13") (pin "2") (pinfunction "22_2") (pintype "passive"))
      (node (ref "R14") (pin "1") (pinfunction "11_1") (pintype "passive"))
      (node (ref "R45") (pin "2") (pinfunction "22_2") (pintype "passive"))
      (node (ref "U10") (pin "12") (pinfunction "VSSA_12") (pintype "bidirectional"))
      (node (ref "U10") (pin "18") (pinfunction "VSS_18") (pintype "bidirectional"))
      (node (ref "U10") (pin "31") (pinfunction "VSS_31") (pintype "bidirectional"))
      (node (ref "U10") (pin "47") (pinfunction "VSS_47") (pintype "bidirectional"))
      (node (ref "U10") (pin "63") (pinfunction "VSS_63") (pintype "bidirectional"))
      (node (ref "U11") (pin "GND") (pinfunction "GND_GND") (pintype "bidirectional"))
      (node (ref "U2") (pin "3") (pinfunction "GND_3") (pintype "power_in"))
      (node (ref "U3") (pin "2") (pinfunction "GND_2") (pintype "power_in"))
      (node (ref "U4") (pin "10") (pinfunction "10_GND_10") (pintype "bidirectional"))
      (node (ref "U4") (pin "12") (pinfunction "12_GND_12") (pintype "bidirectional"))
      (node (ref "U4") (pin "13") (pinfunction "13_GND_13") (pintype "bidirectional"))
      (node (ref "U4") (pin "24") (pinfunction "24_GND_24") (pintype "bidirectional"))
      (node (ref "U4") (pin "7") (pinfunction "7_VDD_USB_7") (pintype "bidirectional"))
      (node (ref "U5") (pin "14") (pinfunction "PGND_14") (pintype "bidirectional"))
      (node (ref "U5") (pin "15") (pinfunction "PGND_15") (pintype "bidirectional"))
      (node (ref "U5") (pin "17") (pinfunction "PGND_17") (pintype "bidirectional"))
      (node (ref "U5") (pin "3") (pinfunction "FREQ_3") (pintype "bidirectional"))
      (node (ref "U5") (pin "5") (pinfunction "FB_5") (pintype "bidirectional"))
      (node (ref "U5") (pin "6") (pinfunction "AGND_6") (pintype "bidirectional"))
      (node (ref "U6") (pin "1") (pinfunction "GND_1") (pintype "bidirectional"))
      (node (ref "U6") (pin "103") (pinfunction "GND_103") (pintype "bidirectional"))
      (node (ref "U6") (pin "104") (pinfunction "GND_104") (pintype "bidirectional"))
      (node (ref "U6") (pin "109") (pinfunction "GND_109") (pintype "bidirectional"))
      (node (ref "U6") (pin "110") (pinfunction "GND_110") (pintype "bidirectional"))
      (node (ref "U6") (pin "115") (pinfunction "GND_115") (pintype "bidirectional"))
      (node (ref "U6") (pin "116") (pinfunction "GND_116") (pintype "bidirectional"))
      (node (ref "U6") (pin "121") (pinfunction "GND_121") (pintype "bidirectional"))
      (node (ref "U6") (pin "122") (pinfunction "GND_122") (pintype "bidirectional"))
      (node (ref "U6") (pin "127") (pinfunction "GND_127") (pintype "bidirectional"))
      (node (ref "U6") (pin "13") (pinfunction "GND_13") (pintype "bidirectional"))
      (node (ref "U6") (pin "133") (pinfunction "GND_133") (pintype "bidirectional"))
      (node (ref "U6") (pin "134") (pinfunction "GND_134") (pintype "bidirectional"))
      (node (ref "U6") (pin "139") (pinfunction "GND_139") (pintype "bidirectional"))
      (node (ref "U6") (pin "14") (pinfunction "GND_14") (pintype "bidirectional"))
      (node (ref "U6") (pin "140") (pinfunction "GND_140") (pintype "bidirectional"))
      (node (ref "U6") (pin "145") (pinfunction "GND_145") (pintype "bidirectional"))
      (node (ref "U6") (pin "146") (pinfunction "GND_146") (pintype "bidirectional"))
      (node (ref "U6") (pin "151") (pinfunction "GND_151") (pintype "bidirectional"))
      (node (ref "U6") (pin "152") (pinfunction "GND_152") (pintype "bidirectional"))
      (node (ref "U6") (pin "157") (pinfunction "GND_157") (pintype "bidirectional"))
      (node (ref "U6") (pin "163") (pinfunction "GND_163") (pintype "bidirectional"))
      (node (ref "U6") (pin "164") (pinfunction "GND_164") (pintype "bidirectional"))
      (node (ref "U6") (pin "169") (pinfunction "GND_169") (pintype "bidirectional"))
      (node (ref "U6") (pin "170") (pinfunction "GND_170") (pintype "bidirectional"))
      (node (ref "U6") (pin "181") (pinfunction "GND_181") (pintype "bidirectional"))
      (node (ref "U6") (pin "182") (pinfunction "GND_182") (pintype "bidirectional"))
      (node (ref "U6") (pin "187") (pinfunction "GND_187") (pintype "bidirectional"))
      (node (ref "U6") (pin "188") (pinfunction "GND_188") (pintype "bidirectional"))
      (node (ref "U6") (pin "19") (pinfunction "GND_19") (pintype "bidirectional"))
      (node (ref "U6") (pin "195") (pinfunction "GND_195") (pintype "bidirectional"))
      (node (ref "U6") (pin "196") (pinfunction "GND_196") (pintype "bidirectional"))
      (node (ref "U6") (pin "20") (pinfunction "GND_20") (pintype "bidirectional"))
      (node (ref "U6") (pin "25") (pinfunction "GND_25") (pintype "bidirectional"))
      (node (ref "U6") (pin "26") (pinfunction "GND_26") (pintype "bidirectional"))
      (node (ref "U6") (pin "31") (pinfunction "GND_31") (pintype "bidirectional"))
      (node (ref "U6") (pin "32") (pinfunction "GND_32") (pintype "bidirectional"))
      (node (ref "U6") (pin "37") (pinfunction "GND_37") (pintype "bidirectional"))
      (node (ref "U6") (pin "38") (pinfunction "GND_38") (pintype "bidirectional"))
      (node (ref "U6") (pin "43") (pinfunction "GND_43") (pintype "bidirectional"))
      (node (ref "U6") (pin "44") (pinfunction "GND_44") (pintype "bidirectional"))
      (node (ref "U6") (pin "49") (pinfunction "GND_49") (pintype "bidirectional"))
      (node (ref "U6") (pin "50") (pinfunction "GND_50") (pintype "bidirectional"))
      (node (ref "U6") (pin "55") (pinfunction "GND_55") (pintype "bidirectional"))
      (node (ref "U6") (pin "56") (pinfunction "GND_56") (pintype "bidirectional"))
      (node (ref "U6") (pin "61") (pinfunction "GND_61") (pintype "bidirectional"))
      (node (ref "U6") (pin "62") (pinfunction "GND_62") (pintype "bidirectional"))
      (node (ref "U6") (pin "67") (pinfunction "GND_67") (pintype "bidirectional"))
      (node (ref "U6") (pin "68") (pinfunction "GND_68") (pintype "bidirectional"))
      (node (ref "U6") (pin "7") (pinfunction "GND_7") (pintype "bidirectional"))
      (node (ref "U6") (pin "73") (pinfunction "GND_73") (pintype "bidirectional"))
      (node (ref "U6") (pin "74") (pinfunction "GND_74") (pintype "bidirectional"))
      (node (ref "U6") (pin "79") (pinfunction "GND_79") (pintype "bidirectional"))
      (node (ref "U6") (pin "8") (pinfunction "GND_8") (pintype "bidirectional"))
      (node (ref "U6") (pin "80") (pinfunction "GND_80") (pintype "bidirectional"))
      (node (ref "U6") (pin "85") (pinfunction "GND_85") (pintype "bidirectional"))
      (node (ref "U6") (pin "86") (pinfunction "GND_86") (pintype "bidirectional"))
      (node (ref "U6") (pin "91") (pinfunction "GND_91") (pintype "bidirectional"))
      (node (ref "U6") (pin "92") (pinfunction "GND_92") (pintype "bidirectional"))
      (node (ref "U6") (pin "97") (pinfunction "GND_97") (pintype "bidirectional"))
      (node (ref "U6") (pin "98") (pinfunction "GND_98") (pintype "bidirectional"))
      (node (ref "U6") (pin "G1") (pinfunction "G1_G1") (pintype "bidirectional"))
      (node (ref "U6") (pin "G2") (pinfunction "G2_G2") (pintype "bidirectional"))
      (node (ref "U7") (pin "6") (pinfunction "AGND_6") (pintype "bidirectional"))
      (node (ref "U7") (pin "8") (pinfunction "PGND_8") (pintype "bidirectional"))
      (node (ref "U7") (pin "EP") (pinfunction "PGND_EP") (pintype "bidirectional"))
      (node (ref "U8") (pin "4") (pinfunction "GND_4") (pintype "bidirectional"))
      (node (ref "U9") (pin "4") (pinfunction "GND_4") (pintype "bidirectional"))
    )
    (net (code "22") (name "GPCLK1") (class "Default")
      (node (ref "J4") (pin "6") (pinfunction "6_6") (pintype "bidirectional"))
      (node (ref "R10") (pin "1") (pinfunction "11_1") (pintype "passive"))
      (node (ref "U6") (pin "82") (pinfunction "GPIO44_82") (pintype "bidirectional"))
    )
    (net (code "23") (name "I2C_MPU_SCL") (class "Default")
      (node (ref "U10") (pin "61") (pinfunction "PB8_61") (pintype "bidirectional"))
      (node (ref "U9") (pin "3") (pinfunction "A1_3") (pintype "bidirectional"))
    )
    (net (code "24") (name "I2C_MPU_SDA") (class "Default")
      (node (ref "U10") (pin "62") (pinfunction "PB9_62") (pintype "bidirectional"))
      (node (ref "U9") (pin "2") (pinfunction "A0_2") (pintype "bidirectional"))
    )
    (net (code "25") (name "I2C_SCL") (class "Default")
      (node (ref "U4") (pin "19") (pinfunction "19_SCL/SPI_CLK_19") (pintype "bidirectional"))
      (node (ref "U6") (pin "11") (pinfunction "GPIO3_11") (pintype "bidirectional"))
      (node (ref "U8") (pin "3") (pinfunction "A1_3") (pintype "bidirectional"))
    )
    (net (code "26") (name "I2C_SCL_1V8") (class "Default")
      (node (ref "J4") (pin "7") (pinfunction "7_7") (pintype "bidirectional"))
      (node (ref "U9") (pin "6") (pinfunction "B1_6") (pintype "bidirectional"))
    )
    (net (code "27") (name "I2C_SCL_5V") (class "Default")
      (node (ref "J1") (pin "2") (pinfunction "2_2") (pintype "bidirectional"))
      (node (ref "J10") (pin "2") (pinfunction "2_2") (pintype "bidirectional"))
      (node (ref "J11") (pin "2") (pinfunction "2_2") (pintype "bidirectional"))
      (node (ref "J2") (pin "2") (pinfunction "2_2") (pintype "bidirectional"))
      (node (ref "J7") (pin "2") (pinfunction "2_2") (pintype "bidirectional"))
      (node (ref "U8") (pin "6") (pinfunction "B1_6") (pintype "bidirectional"))
    )
    (net (code "28") (name "I2C_SDA") (class "Default")
      (node (ref "U4") (pin "18") (pinfunction "18_SDA/SPI_CS_N_18") (pintype "bidirectional"))
      (node (ref "U6") (pin "9") (pinfunction "GPIO2_9") (pintype "bidirectional"))
      (node (ref "U8") (pin "2") (pinfunction "A0_2") (pintype "bidirectional"))
    )
    (net (code "29") (name "I2C_SDA_1V8") (class "Default")
      (node (ref "J4") (pin "8") (pinfunction "8_8") (pintype "bidirectional"))
      (node (ref "U9") (pin "7") (pinfunction "B0_7") (pintype "bidirectional"))
    )
    (net (code "30") (name "I2C_SDA_5V") (class "Default")
      (node (ref "J1") (pin "1") (pinfunction "1_1") (pintype "bidirectional"))
      (node (ref "J10") (pin "1") (pinfunction "1_1") (pintype "bidirectional"))
      (node (ref "J11") (pin "1") (pinfunction "1_1") (pintype "bidirectional"))
      (node (ref "J2") (pin "1") (pinfunction "1_1") (pintype "bidirectional"))
      (node (ref "J7") (pin "1") (pinfunction "1_1") (pintype "bidirectional"))
      (node (ref "U8") (pin "7") (pinfunction "B0_7") (pintype "bidirectional"))
    )
    (net (code "31") (name "ID_SD") (class "Default")
      (node (ref "U11") (pin "CH_PD") (pinfunction "CH_PD_CH_PD") (pintype "bidirectional"))
      (node (ref "U6") (pin "15") (pinfunction "GPIO4_15") (pintype "bidirectional"))
    )
    (net (code "32") (name "INT_A") (class "Default")
      (node (ref "J10") (pin "3") (pinfunction "3_3") (pintype "bidirectional"))
      (node (ref "U6") (pin "64") (pinfunction "GPIO38_64") (pintype "bidirectional"))
    )
    (net (code "33") (name "INT_B") (class "Default")
      (node (ref "J11") (pin "3") (pinfunction "3_3") (pintype "bidirectional"))
      (node (ref "U6") (pin "66") (pinfunction "GPIO39_66") (pintype "bidirectional"))
    )
    (net (code "34") (name "MOTOR1") (class "Default")
      (node (ref "JP2") (pin "1") (pinfunction "1_1") (pintype "passive"))
      (node (ref "U10") (pin "24") (pinfunction "PC4_24") (pintype "bidirectional"))
    )
    (net (code "35") (name "MOTOR2") (class "Default")
      (node (ref "J12") (pin "1") (pinfunction "1_1") (pintype "bidirectional"))
      (node (ref "U10") (pin "25") (pinfunction "PC5_25") (pintype "bidirectional"))
    )
    (net (code "36") (name "MOTOR3") (class "Default")
      (node (ref "J12") (pin "2") (pinfunction "2_2") (pintype "bidirectional"))
      (node (ref "U10") (pin "26") (pinfunction "PB0_26") (pintype "bidirectional"))
    )
    (net (code "37") (name "MOTOR4") (class "Default")
      (node (ref "J12") (pin "3") (pinfunction "3_3") (pintype "bidirectional"))
      (node (ref "U10") (pin "27") (pinfunction "PB1_27") (pintype "bidirectional"))
    )
    (net (code "38") (name "NRST") (class "Default")
      (node (ref "U10") (pin "7") (pinfunction "NRST_7") (pintype "bidirectional"))
      (node (ref "U6") (pin "63") (pinfunction "GPIO18_63") (pintype "bidirectional"))
    )
    (net (code "39") (name "Net-(C15-22)") (class "Default")
      (node (ref "C15") (pin "2") (pinfunction "22_2") (pintype "passive"))
      (node (ref "U2") (pin "2") (pinfunction "CAP_2") (pintype "output"))
    )
    (net (code "40") (name "Net-(C18-11)") (class "Default")
      (node (ref "C18") (pin "1") (pinfunction "11_1") (pintype "passive"))
      (node (ref "U7") (pin "5") (pinfunction "CFF_5") (pintype "bidirectional"))
    )
    (net (code "41") (name "Net-(J5-SIGNAL)") (class "Default")
      (node (ref "J5") (pin "P$3") (pinfunction "SIGNAL_P$3") (pintype "bidirectional"))
      (node (ref "L1") (pin "P$1") (pinfunction "1_P$1") (pintype "passive"))
      (node (ref "U4") (pin "11") (pinfunction "11_RF_IN_11") (pintype "bidirectional"))
    )
    (net (code "42") (name "Net-(L1-2)") (class "Default")
      (node (ref "C4") (pin "2") (pinfunction "2_2") (pintype "bidirectional"))
      (node (ref "L1") (pin "P$2") (pinfunction "2_P$2") (pintype "passive"))
      (node (ref "R12") (pin "2") (pinfunction "22_2") (pintype "passive"))
    )
    (net (code "43") (name "Net-(L2-1)") (class "Default")
      (node (ref "L2") (pin "P$1") (pinfunction "1_P$1") (pintype "passive"))
      (node (ref "U5") (pin "1") (pinfunction "SW_1") (pintype "bidirectional"))
      (node (ref "U5") (pin "2") (pinfunction "SW_2") (pintype "bidirectional"))
    )
    (net (code "44") (name "Net-(L3-1)") (class "Default")
      (node (ref "L3") (pin "P$1") (pinfunction "1_P$1") (pintype "passive"))
      (node (ref "U7") (pin "1") (pinfunction "SW_1") (pintype "bidirectional"))
    )
    (net (code "45") (name "Net-(R1-22)") (class "Default")
      (node (ref "R1") (pin "2") (pinfunction "22_2") (pintype "passive"))
      (node (ref "U3") (pin "6") (pinfunction "FLAG1_6") (pintype "passive"))
      (node (ref "U5") (pin "13") (pinfunction "EN_13") (pintype "bidirectional"))
    )
    (net (code "46") (name "Net-(R2-22)") (class "Default")
      (node (ref "R2") (pin "2") (pinfunction "22_2") (pintype "passive"))
      (node (ref "U3") (pin "5") (pinfunction "FLAG2_5") (pintype "passive"))
      (node (ref "U7") (pin "2") (pinfunction "EN_2") (pintype "bidirectional"))
    )
    (net (code "47") (name "Net-(R3-11)") (class "Default")
      (node (ref "R3") (pin "1") (pinfunction "11_1") (pintype "passive"))
      (node (ref "U11") (pin "CS0") (pinfunction "CS0_CS0") (pintype "bidirectional"))
    )
    (net (code "48") (name "Net-(R5-11)") (class "Default")
      (node (ref "R5") (pin "1") (pinfunction "11_1") (pintype "passive"))
      (node (ref "U11") (pin "MISO") (pinfunction "MISO_MISO") (pintype "bidirectional"))
    )
    (net (code "49") (name "Net-(R6-11)") (class "Default")
      (node (ref "R6") (pin "1") (pinfunction "11_1") (pintype "passive"))
      (node (ref "U11") (pin "GPIO9") (pinfunction "*GPIO9_GPIO9") (pintype "bidirectional"))
    )
    (net (code "50") (name "Net-(R7-11)") (class "Default")
      (node (ref "R7") (pin "1") (pinfunction "11_1") (pintype "passive"))
      (node (ref "U11") (pin "GPIO10") (pinfunction "*GPIO10_GPIO10") (pintype "bidirectional"))
    )
    (net (code "51") (name "Net-(R8-11)") (class "Default")
      (node (ref "R8") (pin "1") (pinfunction "11_1") (pintype "passive"))
      (node (ref "U11") (pin "MOSI") (pinfunction "MOSI_MOSI") (pintype "bidirectional"))
    )
    (net (code "52") (name "Net-(R9-11)") (class "Default")
      (node (ref "R9") (pin "1") (pinfunction "11_1") (pintype "passive"))
      (node (ref "U11") (pin "SCLK") (pinfunction "SCLK_SCLK") (pintype "bidirectional"))
    )
    (net (code "53") (name "Net-(R12-11)") (class "Default")
      (node (ref "R12") (pin "1") (pinfunction "11_1") (pintype "passive"))
      (node (ref "U4") (pin "9") (pinfunction "9_VCC_RF_9") (pintype "bidirectional"))
    )
    (net (code "54") (name "Net-(R14-22)") (class "Default")
      (node (ref "R14") (pin "2") (pinfunction "22_2") (pintype "passive"))
      (node (ref "U10") (pin "60") (pinfunction "BOOT0_60") (pintype "bidirectional"))
    )
    (net (code "55") (name "Net-(R32-11)") (class "Default")
      (node (ref "D1") (pin "A") (pinfunction "A_A") (pintype "passive"))
      (node (ref "R32") (pin "1") (pinfunction "11_1") (pintype "passive"))
    )
    (net (code "56") (name "Net-(R45-11)") (class "Default")
      (node (ref "R45") (pin "1") (pinfunction "11_1") (pintype "passive"))
      (node (ref "U6") (pin "168") (pinfunction "USB_OTGID_168") (pintype "bidirectional"))
    )
    (net (code "57") (name "Net-(U5-CN)") (class "Default")
      (node (ref "C6") (pin "1") (pinfunction "1_1") (pintype "bidirectional"))
      (node (ref "U5") (pin "8") (pinfunction "CN_8") (pintype "bidirectional"))
    )
    (net (code "58") (name "Net-(U5-CP)") (class "Default")
      (node (ref "C6") (pin "2") (pinfunction "2_2") (pintype "bidirectional"))
      (node (ref "U5") (pin "7") (pinfunction "CP_7") (pintype "bidirectional"))
    )
    (net (code "59") (name "Net-(U5-SS)") (class "Default")
      (node (ref "C7") (pin "2") (pinfunction "2_2") (pintype "bidirectional"))
      (node (ref "U5") (pin "9") (pinfunction "SS_9") (pintype "bidirectional"))
    )
    (net (code "60") (name "Net-(U10-VCAP_1)") (class "Default")
      (node (ref "C5") (pin "2") (pinfunction "2_2") (pintype "passive"))
      (node (ref "U10") (pin "30") (pinfunction "VCAP_1_30") (pintype "bidirectional"))
    )
    (net (code "61") (name "POWER_SEQ_EN") (class "Default")
      (node (ref "R4") (pin "2") (pinfunction "22_2") (pintype "passive"))
      (node (ref "U3") (pin "3") (pinfunction "EN_3") (pintype "input"))
    )
    (net (code "62") (name "SCL0") (class "Default")
      (node (ref "J13") (pin "13") (pinfunction "13_13") (pintype "bidirectional"))
      (node (ref "R11") (pin "1") (pinfunction "11_1") (pintype "passive"))
      (node (ref "R16") (pin "2") (pinfunction "22_2") (pintype "passive"))
      (node (ref "U6") (pin "30") (pinfunction "GPIO29_30") (pintype "bidirectional"))
    )
    (net (code "63") (name "SCL1") (class "Default")
      (node (ref "J14") (pin "13") (pinfunction "13_13") (pintype "bidirectional"))
      (node (ref "R18") (pin "2") (pinfunction "22_2") (pintype "passive"))
      (node (ref "U6") (pin "5") (pinfunction "GPIO1_5") (pintype "bidirectional"))
    )
    (net (code "64") (name "SDA0") (class "Default")
      (node (ref "J13") (pin "14") (pinfunction "14_14") (pintype "bidirectional"))
      (node (ref "R13") (pin "1") (pinfunction "11_1") (pintype "passive"))
      (node (ref "R15") (pin "2") (pinfunction "22_2") (pintype "passive"))
      (node (ref "U6") (pin "28") (pinfunction "GPIO28_28") (pintype "bidirectional"))
    )
    (net (code "65") (name "SDA1") (class "Default")
      (node (ref "J14") (pin "14") (pinfunction "14_14") (pintype "bidirectional"))
      (node (ref "R17") (pin "2") (pinfunction "22_2") (pintype "passive"))
      (node (ref "U6") (pin "3") (pinfunction "GPIO0_3") (pintype "bidirectional"))
    )
    (net (code "66") (name "SDX_CLK") (class "Default")
      (node (ref "J8") (pin "5") (pinfunction "CLK_5") (pintype "bidirectional"))
      (node (ref "U6") (pin "10") (pinfunction "SDX_CLK_10") (pintype "bidirectional"))
    )
    (net (code "67") (name "SDX_CMD") (class "Default")
      (node (ref "J8") (pin "3") (pinfunction "CMD_3") (pintype "bidirectional"))
      (node (ref "U6") (pin "12") (pinfunction "SDX_CMD_12") (pintype "bidirectional"))
    )
    (net (code "68") (name "SDX_D0") (class "Default")
      (node (ref "J8") (pin "7") (pinfunction "DAT0_7") (pintype "bidirectional"))
      (node (ref "U6") (pin "16") (pinfunction "SDX_D0_16") (pintype "bidirectional"))
    )
    (net (code "69") (name "SDX_D1") (class "Default")
      (node (ref "J8") (pin "8") (pinfunction "DAT1_8") (pintype "bidirectional"))
      (node (ref "U6") (pin "18") (pinfunction "SDX_D1_18") (pintype "bidirectional"))
    )
    (net (code "70") (name "SDX_D2") (class "Default")
      (node (ref "J8") (pin "1") (pinfunction "DAT2_1") (pintype "bidirectional"))
      (node (ref "U6") (pin "22") (pinfunction "SDX_D2_22") (pintype "bidirectional"))
    )
    (net (code "71") (name "SDX_D3") (class "Default")
      (node (ref "J8") (pin "2") (pinfunction "CD/DAT3_2") (pintype "bidirectional"))
      (node (ref "U6") (pin "24") (pinfunction "SDX_D3_24") (pintype "bidirectional"))
    )
    (net (code "72") (name "SD_CLK") (class "Default")
      (node (ref "R9") (pin "2") (pinfunction "22_2") (pintype "passive"))
      (node (ref "U6") (pin "75") (pinfunction "GPIO22_75") (pintype "bidirectional"))
    )
    (net (code "73") (name "SD_CMD") (class "Default")
      (node (ref "R3") (pin "2") (pinfunction "22_2") (pintype "passive"))
      (node (ref "U6") (pin "77") (pinfunction "GPIO23_77") (pintype "bidirectional"))
    )
    (net (code "74") (name "SD_D0") (class "Default")
      (node (ref "R5") (pin "2") (pinfunction "22_2") (pintype "passive"))
      (node (ref "U6") (pin "81") (pinfunction "GPIO24_81") (pintype "bidirectional"))
    )
    (net (code "75") (name "SD_D1") (class "Default")
      (node (ref "R8") (pin "2") (pinfunction "22_2") (pintype "passive"))
      (node (ref "U6") (pin "83") (pinfunction "GPIO25_83") (pintype "bidirectional"))
    )
    (net (code "76") (name "SD_D2") (class "Default")
      (node (ref "R6") (pin "2") (pinfunction "22_2") (pintype "passive"))
      (node (ref "U6") (pin "87") (pinfunction "GPIO26_87") (pintype "bidirectional"))
    )
    (net (code "77") (name "SD_D3") (class "Default")
      (node (ref "R7") (pin "2") (pinfunction "22_2") (pintype "passive"))
      (node (ref "U6") (pin "89") (pinfunction "GPIO27_89") (pintype "bidirectional"))
    )
    (net (code "78") (name "SERVO1") (class "Default")
      (node (ref "JP1") (pin "1") (pinfunction "1_1") (pintype "passive"))
      (node (ref "U6") (pin "45") (pinfunction "GPIO12_45") (pintype "bidirectional"))
    )
    (net (code "79") (name "SERVO2") (class "Default")
      (node (ref "JP1") (pin "2") (pinfunction "2_2") (pintype "passive"))
      (node (ref "U6") (pin "47") (pinfunction "GPIO13_47") (pintype "bidirectional"))
    )
    (net (code "80") (name "SPI_CS0") (class "Default")
      (node (ref "U2") (pin "5") (pinfunction "~{CS}_5") (pintype "passive"))
      (node (ref "U6") (pin "27") (pinfunction "GPIO8_27") (pintype "bidirectional"))
    )
    (net (code "81") (name "SPI_CS1") (class "Default")
      (node (ref "U10") (pin "20") (pinfunction "PA4_20") (pintype "bidirectional"))
      (node (ref "U6") (pin "23") (pinfunction "GPIO7_23") (pintype "bidirectional"))
    )
    (net (code "82") (name "SPI_MISO") (class "Default")
      (node (ref "U10") (pin "22") (pinfunction "PA6_22") (pintype "bidirectional"))
      (node (ref "U2") (pin "6") (pinfunction "DOUT_6") (pintype "output"))
      (node (ref "U6") (pin "29") (pinfunction "GPIO9_29") (pintype "bidirectional"))
    )
    (net (code "83") (name "SPI_MOSI") (class "Default")
      (node (ref "U10") (pin "23") (pinfunction "PA7_23") (pintype "bidirectional"))
      (node (ref "U2") (pin "7") (pinfunction "DIN_7") (pintype "input"))
      (node (ref "U6") (pin "33") (pinfunction "GPIO10_33") (pintype "bidirectional"))
    )
    (net (code "84") (name "SPI_SCLK") (class "Default")
      (node (ref "U10") (pin "21") (pinfunction "PA5_21") (pintype "bidirectional"))
      (node (ref "U2") (pin "8") (pinfunction "SCLK_8") (pintype "input"))
      (node (ref "U6") (pin "35") (pinfunction "GPIO11_35") (pintype "bidirectional"))
    )
    (net (code "85") (name "SWCLK") (class "Default")
      (node (ref "U10") (pin "49") (pinfunction "PA14_49") (pintype "bidirectional"))
      (node (ref "U6") (pin "69") (pinfunction "GPIO20_69") (pintype "bidirectional"))
    )
    (net (code "86") (name "SWDIO") (class "Default")
      (node (ref "U10") (pin "46") (pinfunction "PA13_46") (pintype "bidirectional"))
      (node (ref "U6") (pin "71") (pinfunction "GPIO21_71") (pintype "bidirectional"))
    )
    (net (code "87") (name "UART2_RX") (class "Default")
      (node (ref "J9") (pin "2") (pinfunction "2_2") (pintype "bidirectional"))
      (node (ref "U6") (pin "72") (pinfunction "GPIO41_72") (pintype "bidirectional"))
    )
    (net (code "88") (name "UART2_TX") (class "Default")
      (node (ref "J9") (pin "1") (pinfunction "1_1") (pintype "bidirectional"))
      (node (ref "U6") (pin "70") (pinfunction "GPIO40_70") (pintype "bidirectional"))
    )
    (net (code "89") (name "USART1_RX") (class "Default")
      (node (ref "J3") (pin "1") (pinfunction "1_1") (pintype "bidirectional"))
      (node (ref "U10") (pin "59") (pinfunction "PB7_59") (pintype "bidirectional"))
      (node (ref "U6") (pin "53") (pinfunction "GPIO15_53") (pintype "bidirectional"))
    )
    (net (code "90") (name "USART1_TX") (class "Default")
      (node (ref "J3") (pin "2") (pinfunction "2_2") (pintype "bidirectional"))
      (node (ref "U6") (pin "51") (pinfunction "GPIO14_51") (pintype "bidirectional"))
    )
    (net (code "91") (name "USB_D_N") (class "Default")
      (node (ref "J4") (pin "4") (pinfunction "4_4") (pintype "bidirectional"))
      (node (ref "U6") (pin "167") (pinfunction "USB_DM_167") (pintype "bidirectional"))
    )
    (net (code "92") (name "USB_D_P") (class "Default")
      (node (ref "J4") (pin "5") (pinfunction "5_5") (pintype "bidirectional"))
      (node (ref "U6") (pin "165") (pinfunction "USB_DP_165") (pintype "bidirectional"))
    )
    (net (code "93") (name "unconnected-(U3-FLAG3-Pad4)") (class "Default")
      (node (ref "U3") (pin "4") (pinfunction "FLAG3_4") (pintype "passive"))
    )
    (net (code "94") (name "unconnected-(U4-1_SAFEBOOT_N-Pad1)") (class "Default")
      (node (ref "U4") (pin "1") (pinfunction "1_SAFEBOOT_N_1") (pintype "bidirectional"))
    )
    (net (code "95") (name "unconnected-(U4-2_D_SEL-Pad2)") (class "Default")
      (node (ref "U4") (pin "2") (pinfunction "2_D_SEL_2") (pintype "bidirectional"))
    )
    (net (code "96") (name "unconnected-(U4-3_TIMEPULSE-Pad3)") (class "Default")
      (node (ref "U4") (pin "3") (pinfunction "3_TIMEPULSE_3") (pintype "bidirectional"))
    )
    (net (code "97") (name "unconnected-(U4-4_EXTINT-Pad4)") (class "Default")
      (node (ref "U4") (pin "4") (pinfunction "4_EXTINT_4") (pintype "bidirectional"))
    )
    (net (code "98") (name "unconnected-(U4-5_USB_DM-Pad5)") (class "Default")
      (node (ref "U4") (pin "5") (pinfunction "5_USB_DM_5") (pintype "bidirectional"))
    )
    (net (code "99") (name "unconnected-(U4-6_USB_DP-Pad6)") (class "Default")
      (node (ref "U4") (pin "6") (pinfunction "6_USB_DP_6") (pintype "bidirectional"))
    )
    (net (code "100") (name "unconnected-(U4-8_RESET_N-Pad8)") (class "Default")
      (node (ref "U4") (pin "8") (pinfunction "8_RESET_N_8") (pintype "bidirectional"))
    )
    (net (code "101") (name "unconnected-(U4-14_LNA_EN{slash}RESERVED-Pad14)") (class "Default")
      (node (ref "U4") (pin "14") (pinfunction "14_LNA_EN/RESERVED_14") (pintype "bidirectional"))
    )
    (net (code "102") (name "unconnected-(U4-15_RESERVED-Pad15)") (class "Default")
      (node (ref "U4") (pin "15") (pinfunction "15_RESERVED_15") (pintype "bidirectional"))
    )
    (net (code "103") (name "unconnected-(U4-16_RESERVED-Pad16)") (class "Default")
      (node (ref "U4") (pin "16") (pinfunction "16_RESERVED_16") (pintype "bidirectional"))
    )
    (net (code "104") (name "unconnected-(U4-17_RESERVED-Pad17)") (class "Default")
      (node (ref "U4") (pin "17") (pinfunction "17_RESERVED_17") (pintype "bidirectional"))
    )
    (net (code "105") (name "unconnected-(U4-20_TXD{slash}SPI_MISO-Pad20)") (class "Default")
      (node (ref "U4") (pin "20") (pinfunction "20_TXD/SPI_MISO_20") (pintype "bidirectional"))
    )
    (net (code "106") (name "unconnected-(U4-21_RXD{slash}SPI_MOSI-Pad21)") (class "Default")
      (node (ref "U4") (pin "21") (pinfunction "21_RXD/SPI_MOSI_21") (pintype "bidirectional"))
    )
    (net (code "107") (name "unconnected-(U5-PG-Pad4)") (class "Default")
      (node (ref "U5") (pin "4") (pinfunction "PG_4") (pintype "bidirectional"))
    )
    (net (code "108") (name "unconnected-(U6-CAM1_DN2-Pad143)") (class "Default")
      (node (ref "U6") (pin "143") (pinfunction "CAM1_DN2_143") (pintype "bidirectional"))
    )
    (net (code "109") (name "unconnected-(U6-CAM1_DN3-Pad137)") (class "Default")
      (node (ref "U6") (pin "137") (pinfunction "CAM1_DN3_137") (pintype "bidirectional"))
    )
    (net (code "110") (name "unconnected-(U6-CAM1_DP2-Pad141)") (class "Default")
      (node (ref "U6") (pin "141") (pinfunction "CAM1_DP2_141") (pintype "bidirectional"))
    )
    (net (code "111") (name "unconnected-(U6-CAM1_DP3-Pad135)") (class "Default")
      (node (ref "U6") (pin "135") (pinfunction "CAM1_DP3_135") (pintype "bidirectional"))
    )
    (net (code "112") (name "unconnected-(U6-DSI0_CN-Pad105)") (class "Default")
      (node (ref "U6") (pin "105") (pinfunction "DSI0_CN_105") (pintype "bidirectional"))
    )
    (net (code "113") (name "unconnected-(U6-DSI0_CP-Pad107)") (class "Default")
      (node (ref "U6") (pin "107") (pinfunction "DSI0_CP_107") (pintype "bidirectional"))
    )
    (net (code "114") (name "unconnected-(U6-DSI0_DN0-Pad99)") (class "Default")
      (node (ref "U6") (pin "99") (pinfunction "DSI0_DN0_99") (pintype "bidirectional"))
    )
    (net (code "115") (name "unconnected-(U6-DSI0_DN1-Pad93)") (class "Default")
      (node (ref "U6") (pin "93") (pinfunction "DSI0_DN1_93") (pintype "bidirectional"))
    )
    (net (code "116") (name "unconnected-(U6-DSI0_DP0-Pad101)") (class "Default")
      (node (ref "U6") (pin "101") (pinfunction "DSI0_DP0_101") (pintype "bidirectional"))
    )
    (net (code "117") (name "unconnected-(U6-DSI0_DP1-Pad95)") (class "Default")
      (node (ref "U6") (pin "95") (pinfunction "DSI0_DP1_95") (pintype "bidirectional"))
    )
    (net (code "118") (name "unconnected-(U6-DSI1_CN-Pad102)") (class "Default")
      (node (ref "U6") (pin "102") (pinfunction "DSI1_CN_102") (pintype "bidirectional"))
    )
    (net (code "119") (name "unconnected-(U6-DSI1_CP-Pad100)") (class "Default")
      (node (ref "U6") (pin "100") (pinfunction "DSI1_CP_100") (pintype "bidirectional"))
    )
    (net (code "120") (name "unconnected-(U6-DSI1_DN0-Pad96)") (class "Default")
      (node (ref "U6") (pin "96") (pinfunction "DSI1_DN0_96") (pintype "bidirectional"))
    )
    (net (code "121") (name "unconnected-(U6-DSI1_DN1-Pad120)") (class "Default")
      (node (ref "U6") (pin "120") (pinfunction "DSI1_DN1_120") (pintype "bidirectional"))
    )
    (net (code "122") (name "unconnected-(U6-DSI1_DN2-Pad114)") (class "Default")
      (node (ref "U6") (pin "114") (pinfunction "DSI1_DN2_114") (pintype "bidirectional"))
    )
    (net (code "123") (name "unconnected-(U6-DSI1_DN3-Pad108)") (class "Default")
      (node (ref "U6") (pin "108") (pinfunction "DSI1_DN3_108") (pintype "bidirectional"))
    )
    (net (code "124") (name "unconnected-(U6-DSI1_DP0-Pad94)") (class "Default")
      (node (ref "U6") (pin "94") (pinfunction "DSI1_DP0_94") (pintype "bidirectional"))
    )
    (net (code "125") (name "unconnected-(U6-DSI1_DP1-Pad118)") (class "Default")
      (node (ref "U6") (pin "118") (pinfunction "DSI1_DP1_118") (pintype "bidirectional"))
    )
    (net (code "126") (name "unconnected-(U6-DSI1_DP2-Pad112)") (class "Default")
      (node (ref "U6") (pin "112") (pinfunction "DSI1_DP2_112") (pintype "bidirectional"))
    )
    (net (code "127") (name "unconnected-(U6-DSI1_DP3-Pad106)") (class "Default")
      (node (ref "U6") (pin "106") (pinfunction "DSI1_DP3_106") (pintype "bidirectional"))
    )
    (net (code "128") (name "unconnected-(U6-EMMC_EN_N_1V8-Pad90)") (class "Default")
      (node (ref "U6") (pin "90") (pinfunction "EMMC_EN_N_1V8_90") (pintype "bidirectional"))
    )
    (net (code "129") (name "unconnected-(U6-GPIO5-Pad17)") (class "Default")
      (node (ref "U6") (pin "17") (pinfunction "GPIO5_17") (pintype "bidirectional"))
    )
    (net (code "130") (name "unconnected-(U6-GPIO6-Pad21)") (class "Default")
      (node (ref "U6") (pin "21") (pinfunction "GPIO6_21") (pintype "bidirectional"))
    )
    (net (code "131") (name "unconnected-(U6-GPIO16-Pad57)") (class "Default")
      (node (ref "U6") (pin "57") (pinfunction "GPIO16_57") (pintype "bidirectional"))
    )
    (net (code "132") (name "unconnected-(U6-GPIO17-Pad59)") (class "Default")
      (node (ref "U6") (pin "59") (pinfunction "GPIO17_59") (pintype "bidirectional"))
    )
    (net (code "133") (name "unconnected-(U6-GPIO19-Pad65)") (class "Default")
      (node (ref "U6") (pin "65") (pinfunction "GPIO19_65") (pintype "bidirectional"))
    )
    (net (code "134") (name "unconnected-(U6-GPIO32-Pad46)") (class "Default")
      (node (ref "U6") (pin "46") (pinfunction "GPIO32_46") (pintype "bidirectional"))
    )
    (net (code "135") (name "unconnected-(U6-GPIO33-Pad48)") (class "Default")
      (node (ref "U6") (pin "48") (pinfunction "GPIO33_48") (pintype "bidirectional"))
    )
    (net (code "136") (name "unconnected-(U6-GPIO34-Pad52)") (class "Default")
      (node (ref "U6") (pin "52") (pinfunction "GPIO34_52") (pintype "bidirectional"))
    )
    (net (code "137") (name "unconnected-(U6-GPIO35-Pad54)") (class "Default")
      (node (ref "U6") (pin "54") (pinfunction "GPIO35_54") (pintype "bidirectional"))
    )
    (net (code "138") (name "unconnected-(U6-GPIO36-Pad58)") (class "Default")
      (node (ref "U6") (pin "58") (pinfunction "GPIO36_58") (pintype "bidirectional"))
    )
    (net (code "139") (name "unconnected-(U6-GPIO37-Pad60)") (class "Default")
      (node (ref "U6") (pin "60") (pinfunction "GPIO37_60") (pintype "bidirectional"))
    )
    (net (code "140") (name "unconnected-(U6-GPIO45-Pad84)") (class "Default")
      (node (ref "U6") (pin "84") (pinfunction "GPIO45_84") (pintype "bidirectional"))
    )
    (net (code "141") (name "unconnected-(U6-HDMI_CEC-Pad171)") (class "Default")
      (node (ref "U6") (pin "171") (pinfunction "HDMI_CEC_171") (pintype "bidirectional"))
    )
    (net (code "142") (name "unconnected-(U6-HDMI_CK_N-Pad111)") (class "Default")
      (node (ref "U6") (pin "111") (pinfunction "HDMI_CK_N_111") (pintype "bidirectional"))
    )
    (net (code "143") (name "unconnected-(U6-HDMI_CK_P-Pad113)") (class "Default")
      (node (ref "U6") (pin "113") (pinfunction "HDMI_CK_P_113") (pintype "bidirectional"))
    )
    (net (code "144") (name "unconnected-(U6-HDMI_D0_N-Pad117)") (class "Default")
      (node (ref "U6") (pin "117") (pinfunction "HDMI_D0_N_117") (pintype "bidirectional"))
    )
    (net (code "145") (name "unconnected-(U6-HDMI_D0_P-Pad119)") (class "Default")
      (node (ref "U6") (pin "119") (pinfunction "HDMI_D0_P_119") (pintype "bidirectional"))
    )
    (net (code "146") (name "unconnected-(U6-HDMI_D1_N-Pad123)") (class "Default")
      (node (ref "U6") (pin "123") (pinfunction "HDMI_D1_N_123") (pintype "bidirectional"))
    )
    (net (code "147") (name "unconnected-(U6-HDMI_D1_P-Pad125)") (class "Default")
      (node (ref "U6") (pin "125") (pinfunction "HDMI_D1_P_125") (pintype "bidirectional"))
    )
    (net (code "148") (name "unconnected-(U6-HDMI_D2_N-Pad129)") (class "Default")
      (node (ref "U6") (pin "129") (pinfunction "HDMI_D2_N_129") (pintype "bidirectional"))
    )
    (net (code "149") (name "unconnected-(U6-HDMI_D2_P-Pad131)") (class "Default")
      (node (ref "U6") (pin "131") (pinfunction "HDMI_D2_P_131") (pintype "bidirectional"))
    )
    (net (code "150") (name "unconnected-(U6-HDMI_HPD_N_1V8-Pad88)") (class "Default")
      (node (ref "U6") (pin "88") (pinfunction "HDMI_HPD_N_1V8_88") (pintype "bidirectional"))
    )
    (net (code "151") (name "unconnected-(U6-HDMI_SCL-Pad175)") (class "Default")
      (node (ref "U6") (pin "175") (pinfunction "HDMI_SCL_175") (pintype "bidirectional"))
    )
    (net (code "152") (name "unconnected-(U6-HDMI_SDA-Pad173)") (class "Default")
      (node (ref "U6") (pin "173") (pinfunction "HDMI_SDA_173") (pintype "bidirectional"))
    )
    (net (code "153") (name "unconnected-(U6-NC-Pad124)") (class "Default")
      (node (ref "U6") (pin "124") (pinfunction "NC_124") (pintype "bidirectional"))
    )
    (net (code "154") (name "unconnected-(U6-NC-Pad126)") (class "Default")
      (node (ref "U6") (pin "126") (pinfunction "NC_126") (pintype "bidirectional"))
    )
    (net (code "155") (name "unconnected-(U6-NC-Pad128)") (class "Default")
      (node (ref "U6") (pin "128") (pinfunction "NC_128") (pintype "bidirectional"))
    )
    (net (code "156") (name "unconnected-(U6-NC-Pad130)") (class "Default")
      (node (ref "U6") (pin "130") (pinfunction "NC_130") (pintype "bidirectional"))
    )
    (net (code "157") (name "unconnected-(U6-NC-Pad132)") (class "Default")
      (node (ref "U6") (pin "132") (pinfunction "NC_132") (pintype "bidirectional"))
    )
    (net (code "158") (name "unconnected-(U6-NC-Pad154)") (class "Default")
      (node (ref "U6") (pin "154") (pinfunction "NC_154") (pintype "bidirectional"))
    )
    (net (code "159") (name "unconnected-(U6-NC-Pad156)") (class "Default")
      (node (ref "U6") (pin "156") (pinfunction "NC_156") (pintype "bidirectional"))
    )
    (net (code "160") (name "unconnected-(U6-NC-Pad158)") (class "Default")
      (node (ref "U6") (pin "158") (pinfunction "NC_158") (pintype "bidirectional"))
    )
    (net (code "161") (name "unconnected-(U6-NC-Pad160)") (class "Default")
      (node (ref "U6") (pin "160") (pinfunction "NC_160") (pintype "bidirectional"))
    )
    (net (code "162") (name "unconnected-(U6-NC-Pad162)") (class "Default")
      (node (ref "U6") (pin "162") (pinfunction "NC_162") (pintype "bidirectional"))
    )
    (net (code "163") (name "unconnected-(U6-RUN-Pad177)") (class "Default")
      (node (ref "U6") (pin "177") (pinfunction "RUN_177") (pintype "bidirectional"))
    )
    (net (code "164") (name "unconnected-(U6-TVDAC-Pad166)") (class "Default")
      (node (ref "U6") (pin "166") (pinfunction "TVDAC_166") (pintype "bidirectional"))
    )
    (net (code "165") (name "unconnected-(U6-VC_TCK-Pad180)") (class "Default")
      (node (ref "U6") (pin "180") (pinfunction "VC_TCK_180") (pintype "bidirectional"))
    )
    (net (code "166") (name "unconnected-(U6-VC_TDI-Pad174)") (class "Default")
      (node (ref "U6") (pin "174") (pinfunction "VC_TDI_174") (pintype "bidirectional"))
    )
    (net (code "167") (name "unconnected-(U6-VC_TDO-Pad178)") (class "Default")
      (node (ref "U6") (pin "178") (pinfunction "VC_TDO_178") (pintype "bidirectional"))
    )
    (net (code "168") (name "unconnected-(U6-VC_TMS-Pad176)") (class "Default")
      (node (ref "U6") (pin "176") (pinfunction "VC_TMS_176") (pintype "bidirectional"))
    )
    (net (code "169") (name "unconnected-(U6-VC_TRST_N-Pad172)") (class "Default")
      (node (ref "U6") (pin "172") (pinfunction "VC_TRST_N_172") (pintype "bidirectional"))
    )
    (net (code "170") (name "unconnected-(U6-VDAC-Pad189)") (class "Default")
      (node (ref "U6") (pin "189") (pinfunction "VDAC_189") (pintype "bidirectional"))
    )
    (net (code "171") (name "unconnected-(U6-VDAC-Pad190)") (class "Default")
      (node (ref "U6") (pin "190") (pinfunction "VDAC_190") (pintype "bidirectional"))
    )
    (net (code "172") (name "unconnected-(U6-VDD_CORE-Pad179)") (class "Default")
      (node (ref "U6") (pin "179") (pinfunction "VDD_CORE_179") (pintype "bidirectional"))
    )
    (net (code "173") (name "unconnected-(U7-NC-Pad3)") (class "Default")
      (node (ref "U7") (pin "3") (pinfunction "NC_3") (pintype "bidirectional"))
    )
    (net (code "174") (name "unconnected-(U10-PA0-Pad14)") (class "Default")
      (node (ref "U10") (pin "14") (pinfunction "PA0_14") (pintype "bidirectional"))
    )
    (net (code "175") (name "unconnected-(U10-PA1-Pad15)") (class "Default")
      (node (ref "U10") (pin "15") (pinfunction "PA1_15") (pintype "bidirectional"))
    )
    (net (code "176") (name "unconnected-(U10-PA2-Pad16)") (class "Default")
      (node (ref "U10") (pin "16") (pinfunction "PA2_16") (pintype "bidirectional"))
    )
    (net (code "177") (name "unconnected-(U10-PA3-Pad17)") (class "Default")
      (node (ref "U10") (pin "17") (pinfunction "PA3_17") (pintype "bidirectional"))
    )
    (net (code "178") (name "unconnected-(U10-PA8-Pad41)") (class "Default")
      (node (ref "U10") (pin "41") (pinfunction "PA8_41") (pintype "bidirectional"))
    )
    (net (code "179") (name "unconnected-(U10-PA9-Pad42)") (class "Default")
      (node (ref "U10") (pin "42") (pinfunction "PA9_42") (pintype "bidirectional"))
    )
    (net (code "180") (name "unconnected-(U10-PA10-Pad43)") (class "Default")
      (node (ref "U10") (pin "43") (pinfunction "PA10_43") (pintype "bidirectional"))
    )
    (net (code "181") (name "unconnected-(U10-PA11-Pad44)") (class "Default")
      (node (ref "U10") (pin "44") (pinfunction "PA11_44") (pintype "bidirectional"))
    )
    (net (code "182") (name "unconnected-(U10-PA12-Pad45)") (class "Default")
      (node (ref "U10") (pin "45") (pinfunction "PA12_45") (pintype "bidirectional"))
    )
    (net (code "183") (name "unconnected-(U10-PA15-Pad50)") (class "Default")
      (node (ref "U10") (pin "50") (pinfunction "PA15_50") (pintype "bidirectional"))
    )
    (net (code "184") (name "unconnected-(U10-PB2-Pad28)") (class "Default")
      (node (ref "U10") (pin "28") (pinfunction "PB2_28") (pintype "bidirectional"))
    )
    (net (code "185") (name "unconnected-(U10-PB3-Pad55)") (class "Default")
      (node (ref "U10") (pin "55") (pinfunction "PB3_55") (pintype "bidirectional"))
    )
    (net (code "186") (name "unconnected-(U10-PB4-Pad56)") (class "Default")
      (node (ref "U10") (pin "56") (pinfunction "PB4_56") (pintype "bidirectional"))
    )
    (net (code "187") (name "unconnected-(U10-PB5-Pad57)") (class "Default")
      (node (ref "U10") (pin "57") (pinfunction "PB5_57") (pintype "bidirectional"))
    )
    (net (code "188") (name "unconnected-(U10-PB6-Pad58)") (class "Default")
      (node (ref "U10") (pin "58") (pinfunction "PB6_58") (pintype "bidirectional"))
    )
    (net (code "189") (name "unconnected-(U10-PB10-Pad29)") (class "Default")
      (node (ref "U10") (pin "29") (pinfunction "PB10_29") (pintype "bidirectional"))
    )
    (net (code "190") (name "unconnected-(U10-PB12-Pad33)") (class "Default")
      (node (ref "U10") (pin "33") (pinfunction "PB12_33") (pintype "bidirectional"))
    )
    (net (code "191") (name "unconnected-(U10-PB13-Pad34)") (class "Default")
      (node (ref "U10") (pin "34") (pinfunction "PB13_34") (pintype "bidirectional"))
    )
    (net (code "192") (name "unconnected-(U10-PB14-Pad35)") (class "Default")
      (node (ref "U10") (pin "35") (pinfunction "PB14_35") (pintype "bidirectional"))
    )
    (net (code "193") (name "unconnected-(U10-PB15-Pad36)") (class "Default")
      (node (ref "U10") (pin "36") (pinfunction "PB15_36") (pintype "bidirectional"))
    )
    (net (code "194") (name "unconnected-(U10-PC0-Pad8)") (class "Default")
      (node (ref "U10") (pin "8") (pinfunction "PC0_8") (pintype "bidirectional"))
    )
    (net (code "195") (name "unconnected-(U10-PC1-Pad9)") (class "Default")
      (node (ref "U10") (pin "9") (pinfunction "PC1_9") (pintype "bidirectional"))
    )
    (net (code "196") (name "unconnected-(U10-PC2-Pad10)") (class "Default")
      (node (ref "U10") (pin "10") (pinfunction "PC2_10") (pintype "bidirectional"))
    )
    (net (code "197") (name "unconnected-(U10-PC3-Pad11)") (class "Default")
      (node (ref "U10") (pin "11") (pinfunction "PC3_11") (pintype "bidirectional"))
    )
    (net (code "198") (name "unconnected-(U10-PC6-Pad37)") (class "Default")
      (node (ref "U10") (pin "37") (pinfunction "PC6_37") (pintype "bidirectional"))
    )
    (net (code "199") (name "unconnected-(U10-PC7-Pad38)") (class "Default")
      (node (ref "U10") (pin "38") (pinfunction "PC7_38") (pintype "bidirectional"))
    )
    (net (code "200") (name "unconnected-(U10-PC8-Pad39)") (class "Default")
      (node (ref "U10") (pin "39") (pinfunction "PC8_39") (pintype "bidirectional"))
    )
    (net (code "201") (name "unconnected-(U10-PC9-Pad40)") (class "Default")
      (node (ref "U10") (pin "40") (pinfunction "PC9_40") (pintype "bidirectional"))
    )
    (net (code "202") (name "unconnected-(U10-PC10-Pad51)") (class "Default")
      (node (ref "U10") (pin "51") (pinfunction "PC10_51") (pintype "bidirectional"))
    )
    (net (code "203") (name "unconnected-(U10-PC11-Pad52)") (class "Default")
      (node (ref "U10") (pin "52") (pinfunction "PC11_52") (pintype "bidirectional"))
    )
    (net (code "204") (name "unconnected-(U10-PC12-Pad53)") (class "Default")
      (node (ref "U10") (pin "53") (pinfunction "PC12_53") (pintype "bidirectional"))
    )
    (net (code "205") (name "unconnected-(U10-PC13-Pad2)") (class "Default")
      (node (ref "U10") (pin "2") (pinfunction "PC13_2") (pintype "bidirectional"))
    )
    (net (code "206") (name "unconnected-(U10-PC14-Pad3)") (class "Default")
      (node (ref "U10") (pin "3") (pinfunction "PC14_3") (pintype "bidirectional"))
    )
    (net (code "207") (name "unconnected-(U10-PC15-Pad4)") (class "Default")
      (node (ref "U10") (pin "4") (pinfunction "PC15_4") (pintype "bidirectional"))
    )
    (net (code "208") (name "unconnected-(U10-PD2-Pad54)") (class "Default")
      (node (ref "U10") (pin "54") (pinfunction "PD2_54") (pintype "bidirectional"))
    )
    (net (code "209") (name "unconnected-(U10-PH0-OSC_IN-Pad5)") (class "Default")
      (node (ref "U10") (pin "5") (pinfunction "PH0-OSC_IN_5") (pintype "bidirectional"))
    )
    (net (code "210") (name "unconnected-(U10-PH1-OSC_OUT-Pad6)") (class "Default")
      (node (ref "U10") (pin "6") (pinfunction "PH1-OSC_OUT_6") (pintype "bidirectional"))
    )
    (net (code "211") (name "unconnected-(U11-PadADC)") (class "Default")
      (node (ref "U11") (pin "ADC") (pinfunction "ADC_ADC") (pintype "bidirectional"))
    )
    (net (code "212") (name "unconnected-(U11-PadGPIO0)") (class "Default")
      (node (ref "U11") (pin "GPIO0") (pinfunction "GPIO0_GPIO0") (pintype "bidirectional"))
    )
    (net (code "213") (name "unconnected-(U11-PadGPIO2)") (class "Default")
      (node (ref "U11") (pin "GPIO2") (pinfunction "GPIO2_GPIO2") (pintype "bidirectional"))
    )
    (net (code "214") (name "unconnected-(U11-PadGPIO5)") (class "Default")
      (node (ref "U11") (pin "GPIO5") (pinfunction "GPIO5_GPIO5") (pintype "bidirectional"))
    )
    (net (code "215") (name "unconnected-(U11-PadGPIO12)") (class "Default")
      (node (ref "U11") (pin "GPIO12") (pinfunction "GPIO12_GPIO12") (pintype "bidirectional"))
    )
    (net (code "216") (name "unconnected-(U11-PadGPIO13)") (class "Default")
      (node (ref "U11") (pin "GPIO13") (pinfunction "GPIO13_GPIO13") (pintype "bidirectional"))
    )
    (net (code "217") (name "unconnected-(U11-PadGPIO14)") (class "Default")
      (node (ref "U11") (pin "GPIO14") (pinfunction "GPIO14_GPIO14") (pintype "bidirectional"))
    )
    (net (code "218") (name "unconnected-(U11-PadGPIO15)") (class "Default")
      (node (ref "U11") (pin "GPIO15") (pinfunction "GPIO15_GPIO15") (pintype "bidirectional"))
    )
    (net (code "219") (name "unconnected-(U11-PadGPIO16)") (class "Default")
      (node (ref "U11") (pin "GPIO16") (pinfunction "GPIO16_GPIO16") (pintype "bidirectional"))
    )
    (net (code "220") (name "unconnected-(U11-PadRESET)") (class "Default")
      (node (ref "U11") (pin "RESET") (pinfunction "RESET_RESET") (pintype "bidirectional"))
    )
    (net (code "221") (name "unconnected-(U11-RX-PadRXD0)") (class "Default")
      (node (ref "U11") (pin "RXD0") (pinfunction "RX_RXD0") (pintype "bidirectional"))
    )
    (net (code "222") (name "unconnected-(U11-TX-PadTXD0)") (class "Default")
      (node (ref "U11") (pin "TXD0") (pinfunction "TX_TXD0") (pintype "bidirectional"))
    )
  )
)
